# Bitcoiner_EB_Project_V1I1_Schematic.net
KiCad netlist of a schematic drawn in Altium Designer
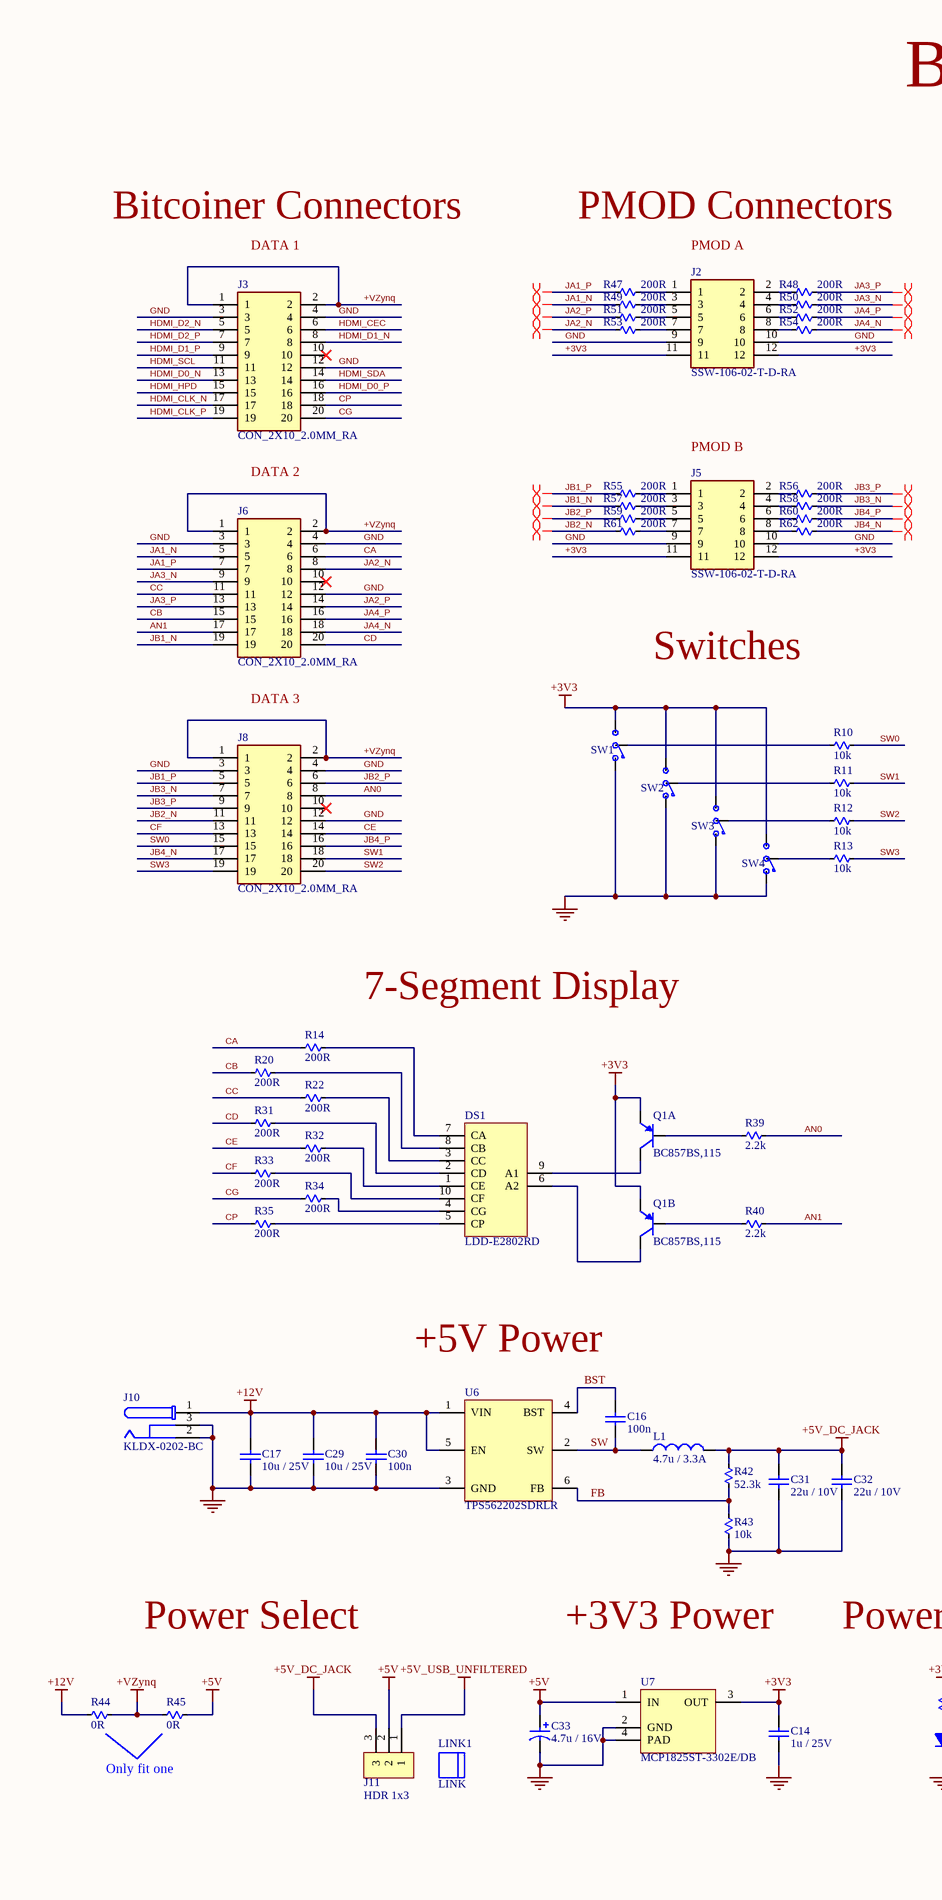
[diagram p0: Bitcoiner_EB_Project_V1I1_Schematic.SchDoc, left]
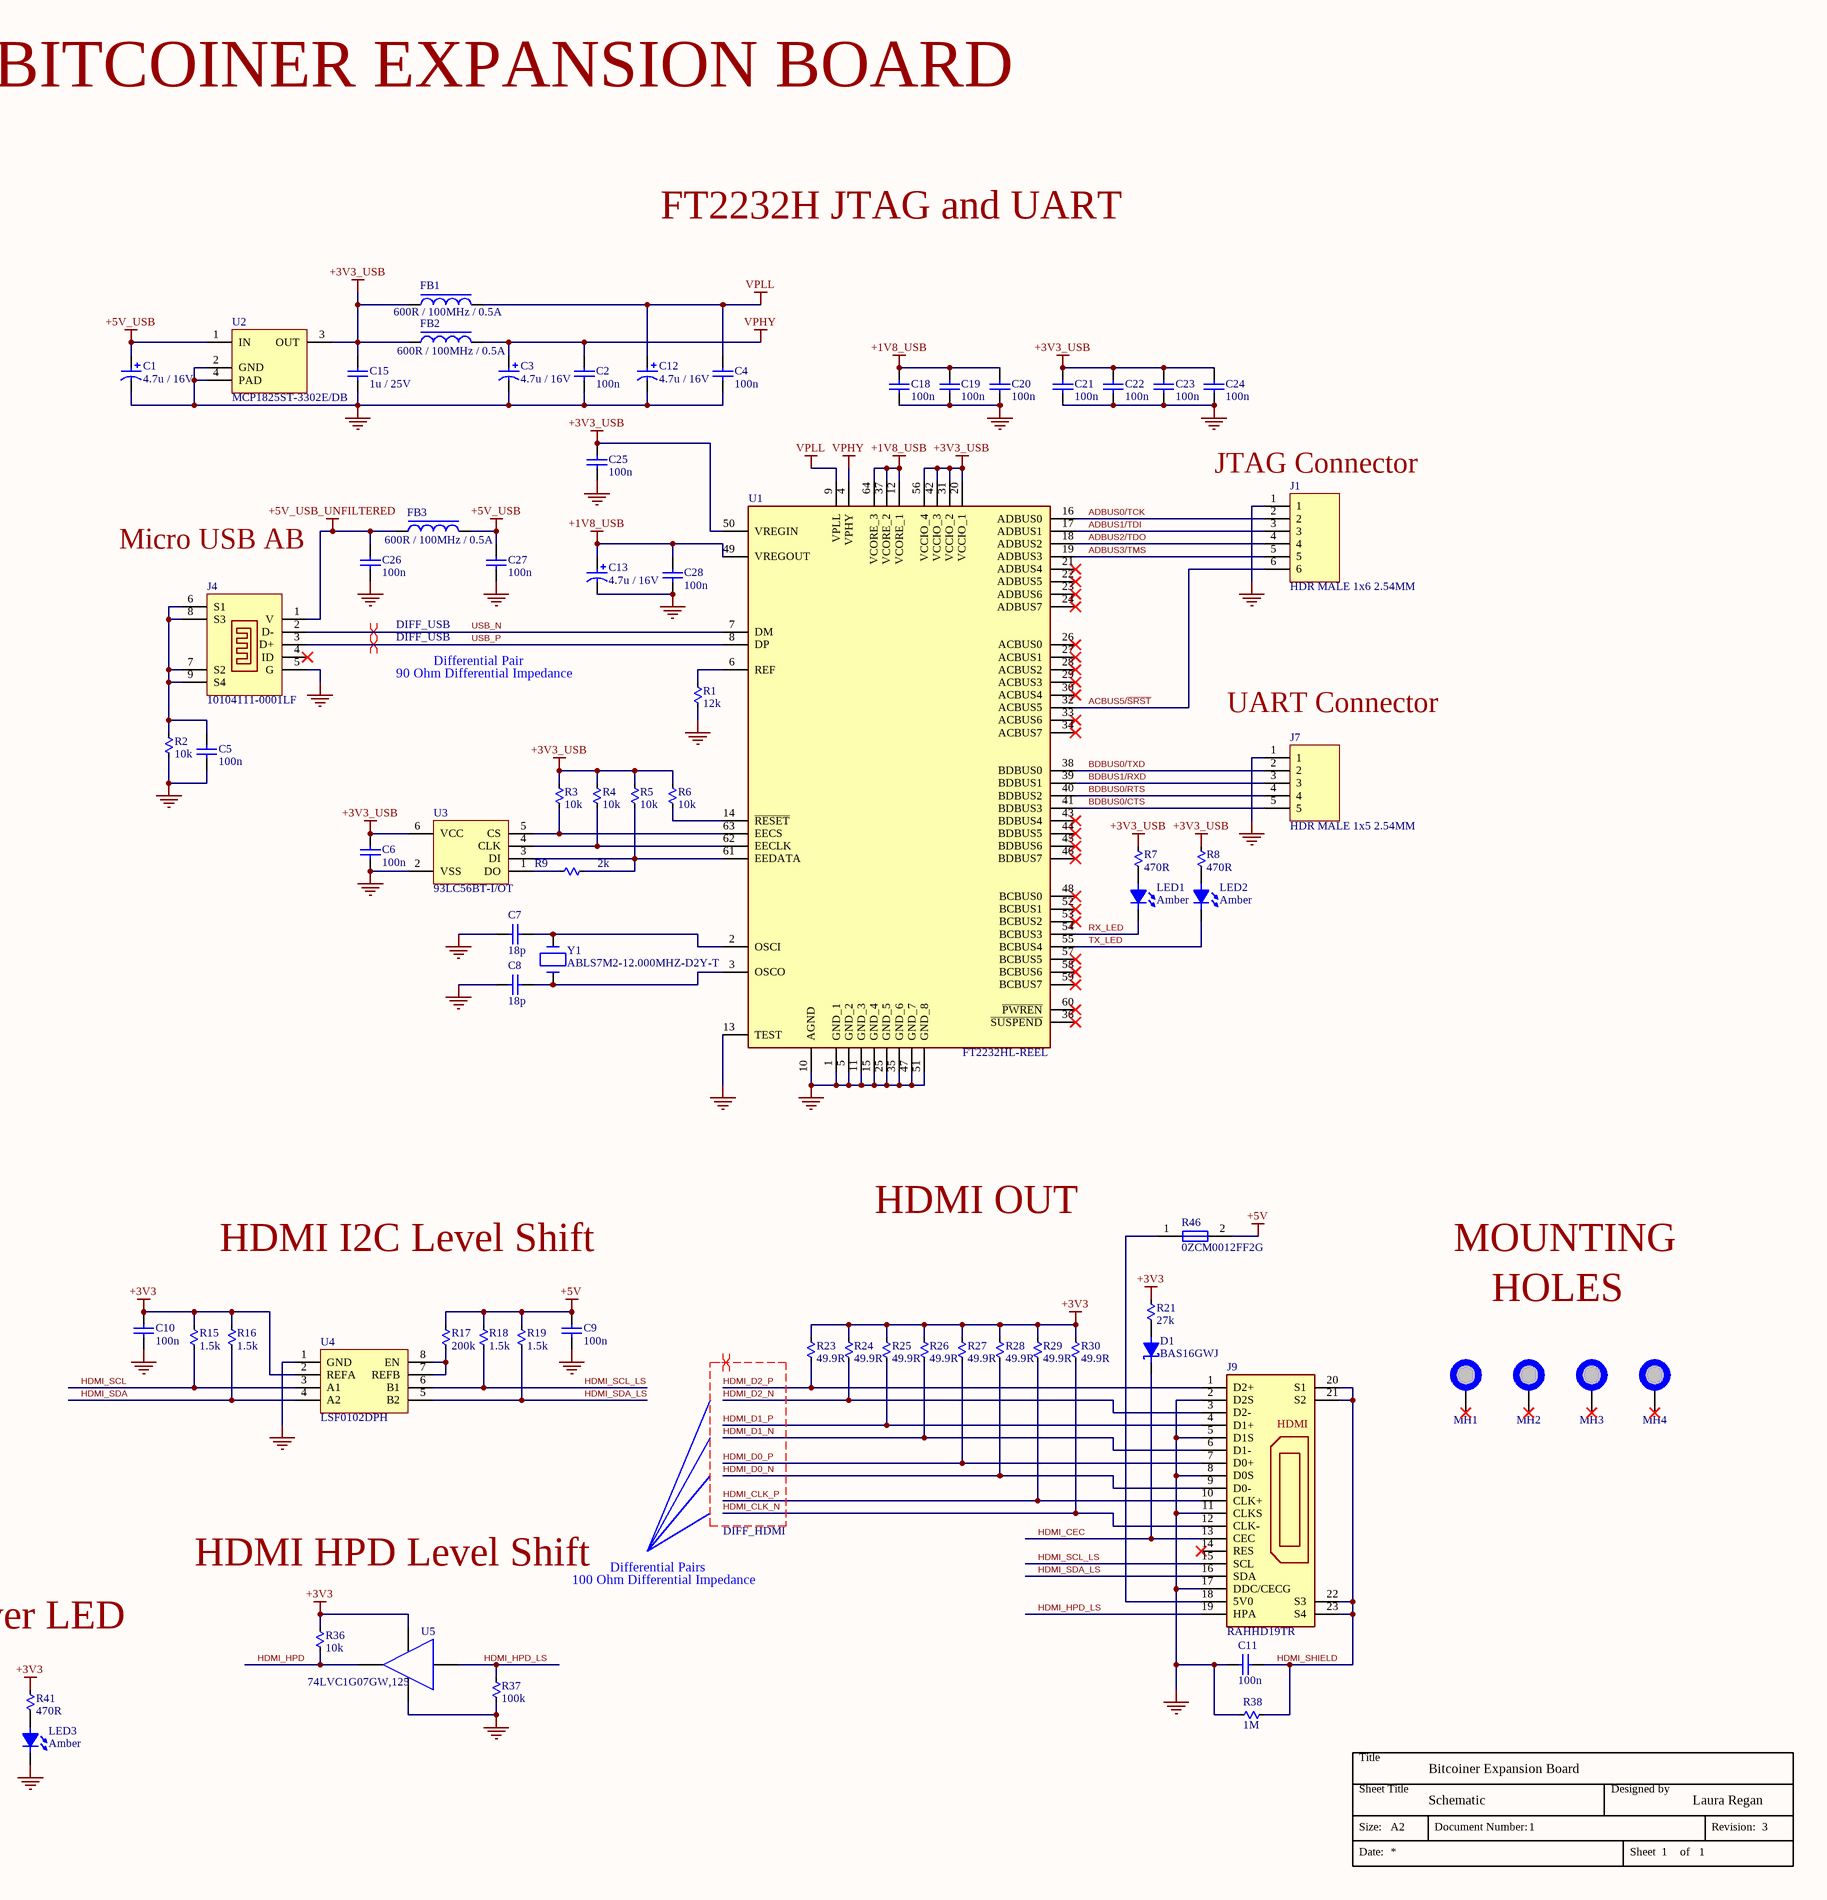
[diagram p1: Bitcoiner_EB_Project_V1I1_Schematic.SchDoc, right]

(export (version "E")
  (design (tool "Eeschema 10.0.6"))
  (components
    (comp (ref "*")
      (value "TitleBlock")
      (fields (field (name "SHEET TITLE") "Schematic") (field (name "SIZE") "A2"))
      (libsource (lib "Bitcoiner_EB_Project_V1I1") (part "TitleBlock"))
    )
    (comp (ref "C1")
      (value "4.7u / 16V")
      (footprint "C_TAN_A")
      (description "Tantalum capacitor 4.7 uF 16 VDC, T491A475K016AT, KEMET")
      (fields
        (field (name "MANUFACTURER") "KEMET")
        (field (name "MANUFACTURER PART NUMBER") "T491A475K016AT")
      )
      (libsource (lib "Bitcoiner_EB_Project_V1I1") (part "T491A475K016AT"))
    )
    (comp (ref "C2")
      (value "100n")
      (footprint "C0805")
      (fields
        (field (name "MANUFACTURER") "Kyocera AVX")
        (field (name "MANUFACTURER PART NUMBER") "08055C104KAT4A")
        (field (name "TOLERANCE") "10%")
      )
      (libsource (lib "Bitcoiner_EB_Project_V1I1") (part "08055C104KAT4A"))
    )
    (comp (ref "C3")
      (value "4.7u / 16V")
      (footprint "C_TAN_A")
      (description "Tantalum capacitor 4.7 uF 16 VDC, T491A475K016AT, KEMET")
      (fields
        (field (name "MANUFACTURER") "KEMET")
        (field (name "MANUFACTURER PART NUMBER") "T491A475K016AT")
      )
      (libsource (lib "Bitcoiner_EB_Project_V1I1") (part "T491A475K016AT"))
    )
    (comp (ref "C4")
      (value "100n")
      (footprint "C0805")
      (fields
        (field (name "MANUFACTURER") "Kyocera AVX")
        (field (name "MANUFACTURER PART NUMBER") "08055C104KAT4A")
        (field (name "TOLERANCE") "10%")
      )
      (libsource (lib "Bitcoiner_EB_Project_V1I1") (part "08055C104KAT4A"))
    )
    (comp (ref "C5")
      (value "100n")
      (footprint "C0805")
      (fields
        (field (name "MANUFACTURER") "Kyocera AVX")
        (field (name "MANUFACTURER PART NUMBER") "08055C104KAT4A")
        (field (name "TOLERANCE") "10%")
      )
      (libsource (lib "Bitcoiner_EB_Project_V1I1") (part "08055C104KAT4A"))
    )
    (comp (ref "C6")
      (value "100n")
      (footprint "C0805")
      (fields
        (field (name "MANUFACTURER") "Kyocera AVX")
        (field (name "MANUFACTURER PART NUMBER") "08055C104KAT4A")
        (field (name "TOLERANCE") "10%")
      )
      (libsource (lib "Bitcoiner_EB_Project_V1I1") (part "08055C104KAT4A"))
    )
    (comp (ref "C7")
      (value "18p")
      (footprint "C0805")
      (description "Cap Ceramic 18pF 50V C0G 5% Pad SMD 0805 125°C Extreme Low ESR Bag")
      (fields
        (field (name "MANUFACTURER") "KEMET")
        (field (name "MANUFACTURER PART NUMBER") "C0805C180J5GAC")
      )
      (libsource (lib "Bitcoiner_EB_Project_V1I1") (part "C0805C180J5GAC"))
    )
    (comp (ref "C8")
      (value "18p")
      (footprint "C0805")
      (description "Cap Ceramic 18pF 50V C0G 5% Pad SMD 0805 125°C Extreme Low ESR Bag")
      (fields
        (field (name "MANUFACTURER") "KEMET")
        (field (name "MANUFACTURER PART NUMBER") "C0805C180J5GAC")
      )
      (libsource (lib "Bitcoiner_EB_Project_V1I1") (part "C0805C180J5GAC"))
    )
    (comp (ref "C9")
      (value "100n")
      (footprint "C0805")
      (fields
        (field (name "MANUFACTURER") "Kyocera AVX")
        (field (name "MANUFACTURER PART NUMBER") "08055C104KAT4A")
        (field (name "TOLERANCE") "10%")
      )
      (libsource (lib "Bitcoiner_EB_Project_V1I1") (part "08055C104KAT4A"))
    )
    (comp (ref "C10")
      (value "100n")
      (footprint "C0805")
      (fields
        (field (name "MANUFACTURER") "Kyocera AVX")
        (field (name "MANUFACTURER PART NUMBER") "08055C104KAT4A")
        (field (name "TOLERANCE") "10%")
      )
      (libsource (lib "Bitcoiner_EB_Project_V1I1") (part "08055C104KAT4A"))
    )
    (comp (ref "C11")
      (value "100n")
      (footprint "C0805")
      (fields
        (field (name "MANUFACTURER") "Kyocera AVX")
        (field (name "MANUFACTURER PART NUMBER") "08055C104KAT4A")
        (field (name "TOLERANCE") "10%")
      )
      (libsource (lib "Bitcoiner_EB_Project_V1I1") (part "08055C104KAT4A"))
    )
    (comp (ref "C12")
      (value "4.7u / 16V")
      (footprint "C_TAN_A")
      (description "Tantalum capacitor 4.7 uF 16 VDC, T491A475K016AT, KEMET")
      (fields
        (field (name "MANUFACTURER") "KEMET")
        (field (name "MANUFACTURER PART NUMBER") "T491A475K016AT")
      )
      (libsource (lib "Bitcoiner_EB_Project_V1I1") (part "T491A475K016AT"))
    )
    (comp (ref "C13")
      (value "4.7u / 16V")
      (footprint "C_TAN_A")
      (description "Tantalum capacitor 4.7 uF 16 VDC, T491A475K016AT, KEMET")
      (fields
        (field (name "MANUFACTURER") "KEMET")
        (field (name "MANUFACTURER PART NUMBER") "T491A475K016AT")
      )
      (libsource (lib "Bitcoiner_EB_Project_V1I1") (part "T491A475K016AT"))
    )
    (comp (ref "C14")
      (value "1u / 25V")
      (footprint "C0805")
      (description "Cap Ceramic 1uF 25V X7R 10% SMD 0805 125C Plastic T/R")
      (fields
        (field (name "MANUFACTURER") "KEMET")
        (field (name "MANUFACTURER PART NUMBER") "C0805C105K3RAC7210")
      )
      (libsource (lib "Bitcoiner_EB_Project_V1I1") (part "C0805C105K3RAC7210"))
    )
    (comp (ref "C15")
      (value "1u / 25V")
      (footprint "C0805")
      (description "Cap Ceramic 1uF 25V X7R 10% SMD 0805 125C Plastic T/R")
      (fields
        (field (name "MANUFACTURER") "KEMET")
        (field (name "MANUFACTURER PART NUMBER") "C0805C105K3RAC7210")
      )
      (libsource (lib "Bitcoiner_EB_Project_V1I1") (part "C0805C105K3RAC7210"))
    )
    (comp (ref "C16")
      (value "100n")
      (footprint "C0805")
      (fields
        (field (name "MANUFACTURER") "Kyocera AVX")
        (field (name "MANUFACTURER PART NUMBER") "08055C104KAT4A")
        (field (name "TOLERANCE") "10%")
      )
      (libsource (lib "Bitcoiner_EB_Project_V1I1") (part "08055C104KAT4A"))
    )
    (comp (ref "C17")
      (value "10u / 25V")
      (footprint "C0805")
      (description "CAP CER 10UF 25V X5R 0805")
      (fields
        (field (name "MANUFACTURER") "Murata")
        (field (name "MANUFACTURER PART NUMBER") "GRM21BR61E106KA73K")
      )
      (libsource (lib "Bitcoiner_EB_Project_V1I1") (part "GRM21BR61E106KA73K"))
    )
    (comp (ref "C18")
      (value "100n")
      (footprint "C0805")
      (fields
        (field (name "MANUFACTURER") "Kyocera AVX")
        (field (name "MANUFACTURER PART NUMBER") "08055C104KAT4A")
        (field (name "TOLERANCE") "10%")
      )
      (libsource (lib "Bitcoiner_EB_Project_V1I1") (part "08055C104KAT4A"))
    )
    (comp (ref "C19")
      (value "100n")
      (footprint "C0805")
      (fields
        (field (name "MANUFACTURER") "Kyocera AVX")
        (field (name "MANUFACTURER PART NUMBER") "08055C104KAT4A")
        (field (name "TOLERANCE") "10%")
      )
      (libsource (lib "Bitcoiner_EB_Project_V1I1") (part "08055C104KAT4A"))
    )
    (comp (ref "C20")
      (value "100n")
      (footprint "C0805")
      (fields
        (field (name "MANUFACTURER") "Kyocera AVX")
        (field (name "MANUFACTURER PART NUMBER") "08055C104KAT4A")
        (field (name "TOLERANCE") "10%")
      )
      (libsource (lib "Bitcoiner_EB_Project_V1I1") (part "08055C104KAT4A"))
    )
    (comp (ref "C21")
      (value "100n")
      (footprint "C0805")
      (fields
        (field (name "MANUFACTURER") "Kyocera AVX")
        (field (name "MANUFACTURER PART NUMBER") "08055C104KAT4A")
        (field (name "TOLERANCE") "10%")
      )
      (libsource (lib "Bitcoiner_EB_Project_V1I1") (part "08055C104KAT4A"))
    )
    (comp (ref "C22")
      (value "100n")
      (footprint "C0805")
      (fields
        (field (name "MANUFACTURER") "Kyocera AVX")
        (field (name "MANUFACTURER PART NUMBER") "08055C104KAT4A")
        (field (name "TOLERANCE") "10%")
      )
      (libsource (lib "Bitcoiner_EB_Project_V1I1") (part "08055C104KAT4A"))
    )
    (comp (ref "C23")
      (value "100n")
      (footprint "C0805")
      (fields
        (field (name "MANUFACTURER") "Kyocera AVX")
        (field (name "MANUFACTURER PART NUMBER") "08055C104KAT4A")
        (field (name "TOLERANCE") "10%")
      )
      (libsource (lib "Bitcoiner_EB_Project_V1I1") (part "08055C104KAT4A"))
    )
    (comp (ref "C24")
      (value "100n")
      (footprint "C0805")
      (fields
        (field (name "MANUFACTURER") "Kyocera AVX")
        (field (name "MANUFACTURER PART NUMBER") "08055C104KAT4A")
        (field (name "TOLERANCE") "10%")
      )
      (libsource (lib "Bitcoiner_EB_Project_V1I1") (part "08055C104KAT4A"))
    )
    (comp (ref "C25")
      (value "100n")
      (footprint "C0805")
      (fields
        (field (name "MANUFACTURER") "Kyocera AVX")
        (field (name "MANUFACTURER PART NUMBER") "08055C104KAT4A")
        (field (name "TOLERANCE") "10%")
      )
      (libsource (lib "Bitcoiner_EB_Project_V1I1") (part "08055C104KAT4A"))
    )
    (comp (ref "C26")
      (value "100n")
      (footprint "C0805")
      (fields
        (field (name "MANUFACTURER") "Kyocera AVX")
        (field (name "MANUFACTURER PART NUMBER") "08055C104KAT4A")
        (field (name "TOLERANCE") "10%")
      )
      (libsource (lib "Bitcoiner_EB_Project_V1I1") (part "08055C104KAT4A"))
    )
    (comp (ref "C27")
      (value "100n")
      (footprint "C0805")
      (fields
        (field (name "MANUFACTURER") "Kyocera AVX")
        (field (name "MANUFACTURER PART NUMBER") "08055C104KAT4A")
        (field (name "TOLERANCE") "10%")
      )
      (libsource (lib "Bitcoiner_EB_Project_V1I1") (part "08055C104KAT4A"))
    )
    (comp (ref "C28")
      (value "100n")
      (footprint "C0805")
      (fields
        (field (name "MANUFACTURER") "Kyocera AVX")
        (field (name "MANUFACTURER PART NUMBER") "08055C104KAT4A")
        (field (name "TOLERANCE") "10%")
      )
      (libsource (lib "Bitcoiner_EB_Project_V1I1") (part "08055C104KAT4A"))
    )
    (comp (ref "C29")
      (value "10u / 25V")
      (footprint "C0805")
      (description "CAP CER 10UF 25V X5R 0805")
      (fields
        (field (name "MANUFACTURER") "Murata")
        (field (name "MANUFACTURER PART NUMBER") "GRM21BR61E106KA73K")
      )
      (libsource (lib "Bitcoiner_EB_Project_V1I1") (part "GRM21BR61E106KA73K"))
    )
    (comp (ref "C30")
      (value "100n")
      (footprint "C0805")
      (fields
        (field (name "MANUFACTURER") "Kyocera AVX")
        (field (name "MANUFACTURER PART NUMBER") "08055C104KAT4A")
        (field (name "TOLERANCE") "10%")
      )
      (libsource (lib "Bitcoiner_EB_Project_V1I1") (part "08055C104KAT4A"))
    )
    (comp (ref "C31")
      (value "22u / 10V")
      (footprint "C0805")
      (description "Cap Ceramic 22uF 10V X5R 20% SMD 0805 85C Cardboard T/R")
      (fields
        (field (name "MANUFACTURER") "Samsung")
        (field (name "MANUFACTURER PART NUMBER") "CL21A226MPCLRNC")
      )
      (libsource (lib "Bitcoiner_EB_Project_V1I1") (part "CL21A226MPCLRNC"))
    )
    (comp (ref "C32")
      (value "22u / 10V")
      (footprint "C0805")
      (description "Cap Ceramic 22uF 10V X5R 20% SMD 0805 85C Cardboard T/R")
      (fields
        (field (name "MANUFACTURER") "Samsung")
        (field (name "MANUFACTURER PART NUMBER") "CL21A226MPCLRNC")
      )
      (libsource (lib "Bitcoiner_EB_Project_V1I1") (part "CL21A226MPCLRNC"))
    )
    (comp (ref "C33")
      (value "4.7u / 16V")
      (footprint "C_TAN_A")
      (description "Tantalum capacitor 4.7 uF 16 VDC, T491A475K016AT, KEMET")
      (fields
        (field (name "MANUFACTURER") "KEMET")
        (field (name "MANUFACTURER PART NUMBER") "T491A475K016AT")
      )
      (libsource (lib "Bitcoiner_EB_Project_V1I1") (part "T491A475K016AT"))
    )
    (comp (ref "D1")
      (value "BAS16GWJ")
      (footprint "SOD123")
      (description "High-speed switching diode BAS16GW/SOD2/REEL 13 Q1/T1 S\"")
      (fields (field (name "MANUFACTURER") "Nexperia"))
      (libsource (lib "Bitcoiner_EB_Project_V1I1") (part "BAS16GWJ"))
    )
    (comp (ref "DS1")
      (value "LDD-E2802RD")
      (footprint "LDD-E2802RD")
      (description "Dual Digit 565 nm Green 0.28 inch Common Anode Seven Segment Display")
      (fields (field (name "MANUFACTURER") "Lumex"))
      (libsource (lib "Bitcoiner_EB_Project_V1I1") (part "LDD-E2802RD"))
    )
    (comp (ref "FB1")
      (value "600R / 100MHz / 0.5A")
      (footprint "R0805")
      (description "TDK         MMZ2012R601AT000            FERRITE BEAD, 0.2OHM, 500MA, 0805")
      (fields
        (field (name "MANUFACTURER") "TDK")
        (field (name "MANUFACTURER PART NUMBER") "MMZ2012R601AT000")
      )
      (libsource (lib "Bitcoiner_EB_Project_V1I1") (part "MMZ2012R601AT000"))
    )
    (comp (ref "FB2")
      (value "600R / 100MHz / 0.5A")
      (footprint "R0805")
      (description "TDK         MMZ2012R601AT000            FERRITE BEAD, 0.2OHM, 500MA, 0805")
      (fields
        (field (name "MANUFACTURER") "TDK")
        (field (name "MANUFACTURER PART NUMBER") "MMZ2012R601AT000")
      )
      (libsource (lib "Bitcoiner_EB_Project_V1I1") (part "MMZ2012R601AT000"))
    )
    (comp (ref "FB3")
      (value "600R / 100MHz / 0.5A")
      (footprint "R0805")
      (description "TDK         MMZ2012R601AT000            FERRITE BEAD, 0.2OHM, 500MA, 0805")
      (fields
        (field (name "MANUFACTURER") "TDK")
        (field (name "MANUFACTURER PART NUMBER") "MMZ2012R601AT000")
      )
      (libsource (lib "Bitcoiner_EB_Project_V1I1") (part "MMZ2012R601AT000"))
    )
    (comp (ref "J1")
      (value "HDR MALE 1x6 2.54MM")
      (footprint "HDR_MALE_1X6_2.54MM")
      (fields
        (field (name "MANUFACTURER") "Amphenol")
        (field (name "MANUFACTURER PART NUMBER") "G800W302018EU")
      )
      (libsource (lib "Bitcoiner_EB_Project_V1I1") (part "G800W302018EU"))
    )
    (comp (ref "J2")
      (value "SSW-106-02-T-D-RA")
      (footprint "SSW-106-XX-YYY-D-RA")
      (description "Connector")
      (fields (field (name "MOUSER2 PART NUMBER") "200-SSW10602TDRA") (field (name "MANUFACTURER") "SAMTEC"))
      (libsource (lib "Bitcoiner_EB_Project_V1I1") (part "SSW-106-02-T-D-RA"))
    )
    (comp (ref "J3")
      (value "CON_2X10_2.0MM_RA")
      (footprint "CON_2X10_2.0MM_RA")
      (libsource (lib "Bitcoiner_EB_Project_V1I1") (part "CON_2X10_2.0MM_RA"))
    )
    (comp (ref "J4")
      (value "10104111-0001LF")
      (footprint "101041110001LF")
      (description "Conn USB Type A/B RCP 5 POS 0.65mm Solder RA SMD 5 Terminal 1 Port T/R")
      (fields (field (name "MANUFACTURER") "AMPHENOL ICC (FCI)"))
      (libsource (lib "Bitcoiner_EB_Project_V1I1") (part "10104111-0001LF"))
    )
    (comp (ref "J5")
      (value "SSW-106-02-T-D-RA")
      (footprint "SSW-106-XX-YYY-D-RA")
      (description "Connector")
      (fields (field (name "MOUSER2 PART NUMBER") "200-SSW10602TDRA") (field (name "MANUFACTURER") "SAMTEC"))
      (libsource (lib "Bitcoiner_EB_Project_V1I1") (part "SSW-106-02-T-D-RA"))
    )
    (comp (ref "J6")
      (value "CON_2X10_2.0MM_RA")
      (footprint "CON_2X10_2.0MM_RA")
      (libsource (lib "Bitcoiner_EB_Project_V1I1") (part "CON_2X10_2.0MM_RA"))
    )
    (comp (ref "J7")
      (value "HDR MALE 1x5 2.54MM")
      (footprint "Hdr_Female_1x5_2.54mm")
      (description "HDR FEMALE 1x5 2.54MM")
      (fields
        (field (name "MANUFACTURER") "Amphenol ICC")
        (field (name "MANUFACTURER PART NUMBER") "10129378-905001BLF")
      )
      (libsource (lib "Bitcoiner_EB_Project_V1I1") (part "10129378-905001BLF"))
    )
    (comp (ref "J8")
      (value "CON_2X10_2.0MM_RA")
      (footprint "CON_2X10_2.0MM_RA")
      (libsource (lib "Bitcoiner_EB_Project_V1I1") (part "CON_2X10_2.0MM_RA"))
    )
    (comp (ref "J9")
      (value "RAHHD19TR")
      (footprint "RAHHD19TR")
      (description "HDMI Connector")
      (fields (field (name "MANUFACTURER") "Switchcraft Conxall"))
      (libsource (lib "Bitcoiner_EB_Project_V1I1") (part "RAHHD19TR"))
    )
    (comp (ref "J10")
      (value "KLDX-0202-BC")
      (footprint "KLDX-0202-BC")
      (description "Conn Power PIN 2 POS Solder RA Thru-Hole 3 Terminal 1 Port")
      (fields (field (name "MANUFACTURER") "Kycon"))
      (libsource (lib "Bitcoiner_EB_Project_V1I1") (part "KLDX-0202-BC"))
    )
    (comp (ref "J11")
      (value "HDR 1x3")
      (footprint "HDR_Male_1x3_2.54mm")
      (description "HDR MALE 1x3 2.54MM")
      (fields
        (field (name "MANUFACTURER") "Amphenol")
        (field (name "MANUFACTURER PART NUMBER") "G800W305018EU")
      )
      (libsource (lib "Bitcoiner_EB_Project_V1I1") (part "G800W305018EU"))
    )
    (comp (ref "L1")
      (value "4.7u / 3.3A")
      (footprint "TYS6045")
      (description "Pwrind, SMT, Shld, Lrated / 6.0X6.0X4.5MM / Uom=ea / Wire Wound Inductive / Fixed Inductor")
      (fields
        (field (name "MANUFACTURER") "Laird Steward")
        (field (name "MANUFACTURER PART NUMBER") "TYS60454R7M-10")
      )
      (libsource (lib "Bitcoiner_EB_Project_V1I1") (part "TYS60454R7M-10"))
    )
    (comp (ref "LED1")
      (value "Amber")
      (footprint "LED0603")
      (description "LED Uni-Color Amber 609nm Automotive 2-Pin Chip 0603(1608Metric) T/R")
      (fields (field (name "MANUFACTURER") "Inolux") (field (name "MANUFACTURER PART NUMBER") "IN-S63AT5A"))
      (libsource (lib "Bitcoiner_EB_Project_V1I1") (part "IN-S63AT5A"))
    )
    (comp (ref "LED2")
      (value "Amber")
      (footprint "LED0603")
      (description "LED Uni-Color Amber 609nm Automotive 2-Pin Chip 0603(1608Metric) T/R")
      (fields (field (name "MANUFACTURER") "Inolux") (field (name "MANUFACTURER PART NUMBER") "IN-S63AT5A"))
      (libsource (lib "Bitcoiner_EB_Project_V1I1") (part "IN-S63AT5A"))
    )
    (comp (ref "LED3")
      (value "Amber")
      (footprint "LED0603")
      (description "LED Uni-Color Amber 609nm Automotive 2-Pin Chip 0603(1608Metric) T/R")
      (fields (field (name "MANUFACTURER") "Inolux") (field (name "MANUFACTURER PART NUMBER") "IN-S63AT5A"))
      (libsource (lib "Bitcoiner_EB_Project_V1I1") (part "IN-S63AT5A"))
    )
    (comp (ref "LINK1")
      (value "LINK")
      (description "CONN SHUNT 2POS OPEN 2.54MM")
      (fields
        (field (name "MANUFACTURER") "TE Connectivity")
        (field (name "MANUFACTURER PART NUMBER") "382811-8")
      )
      (libsource (lib "Bitcoiner_EB_Project_V1I1") (part "382811-8"))
    )
    (comp (ref "MH1")
      (value "MH_7.4MMNC_3.2MMD")
      (footprint "MH_7.4MMD_3.2MMD_NON_COPPER_NPTH")
      (description "Mounting Hole 7.4mm Diameter (Non Copper), 3.2 Drill NPTH")
      (libsource (lib "Bitcoiner_EB_Project_V1I1") (part "MH_7.4MMNC_3.2MMD"))
    )
    (comp (ref "MH2")
      (value "MH_7.4MMNC_3.2MMD")
      (footprint "MH_7.4MMD_3.2MMD_NON_COPPER_NPTH")
      (description "Mounting Hole 7.4mm Diameter (Non Copper), 3.2 Drill NPTH")
      (libsource (lib "Bitcoiner_EB_Project_V1I1") (part "MH_7.4MMNC_3.2MMD"))
    )
    (comp (ref "MH3")
      (value "MH_7.4MMNC_3.2MMD")
      (footprint "MH_7.4MMD_3.2MMD_NON_COPPER_NPTH")
      (description "Mounting Hole 7.4mm Diameter (Non Copper), 3.2 Drill NPTH")
      (libsource (lib "Bitcoiner_EB_Project_V1I1") (part "MH_7.4MMNC_3.2MMD"))
    )
    (comp (ref "MH4")
      (value "MH_7.4MMNC_3.2MMD")
      (footprint "MH_7.4MMD_3.2MMD_NON_COPPER_NPTH")
      (description "Mounting Hole 7.4mm Diameter (Non Copper), 3.2 Drill NPTH")
      (libsource (lib "Bitcoiner_EB_Project_V1I1") (part "MH_7.4MMNC_3.2MMD"))
    )
    (comp (ref "Q1")
      (value "BC857BS,115")
      (footprint "SOT363")
      (description "NEXPERIA - BC857BS,115 - TRANSISTOR, DUAL, PNP, SC-88")
      (fields (field (name "MANUFACTURER") "Nexperia"))
      (libsource (lib "Bitcoiner_EB_Project_V1I1") (part "BC857BS,115"))
    )
    (comp (ref "R1")
      (value "12k")
      (footprint "R0805")
      (description "Res Thick Film 0805 12K Ohm 1% 0.125W(1/8W) ±100ppm/C Molded SMD Paper T/R")
      (fields
        (field (name "MANUFACTURER") "Yageo")
        (field (name "MANUFACTURER PART NUMBER") "RC0805FR-0712KL")
      )
      (libsource (lib "Bitcoiner_EB_Project_V1I1") (part "RC0805FR-0712KL"))
    )
    (comp (ref "R2")
      (value "10k")
      (footprint "R0805")
      (description "RES SMD 10K OHM 1% 1/8W 0805")
      (fields
        (field (name "MANUFACTURER") "Yageo")
        (field (name "MANUFACTURER PART NUMBER") "RC0805FR-0710KL")
      )
      (libsource (lib "Bitcoiner_EB_Project_V1I1") (part "RC0805FR-0710KL"))
    )
    (comp (ref "R3")
      (value "10k")
      (footprint "R0805")
      (description "RES SMD 10K OHM 1% 1/8W 0805")
      (fields
        (field (name "MANUFACTURER") "Yageo")
        (field (name "MANUFACTURER PART NUMBER") "RC0805FR-0710KL")
      )
      (libsource (lib "Bitcoiner_EB_Project_V1I1") (part "RC0805FR-0710KL"))
    )
    (comp (ref "R4")
      (value "10k")
      (footprint "R0805")
      (description "RES SMD 10K OHM 1% 1/8W 0805")
      (fields
        (field (name "MANUFACTURER") "Yageo")
        (field (name "MANUFACTURER PART NUMBER") "RC0805FR-0710KL")
      )
      (libsource (lib "Bitcoiner_EB_Project_V1I1") (part "RC0805FR-0710KL"))
    )
    (comp (ref "R5")
      (value "10k")
      (footprint "R0805")
      (description "RES SMD 10K OHM 1% 1/8W 0805")
      (fields
        (field (name "MANUFACTURER") "Yageo")
        (field (name "MANUFACTURER PART NUMBER") "RC0805FR-0710KL")
      )
      (libsource (lib "Bitcoiner_EB_Project_V1I1") (part "RC0805FR-0710KL"))
    )
    (comp (ref "R6")
      (value "10k")
      (footprint "R0805")
      (description "RES SMD 10K OHM 1% 1/8W 0805")
      (fields
        (field (name "MANUFACTURER") "Yageo")
        (field (name "MANUFACTURER PART NUMBER") "RC0805FR-0710KL")
      )
      (libsource (lib "Bitcoiner_EB_Project_V1I1") (part "RC0805FR-0710KL"))
    )
    (comp (ref "R7")
      (value "470R")
      (footprint "R0805")
      (description "Res Thick Film 0805 470 Ohm 1% 1/8W +/-100ppm/ßC Molded SMD Paper T/R")
      (fields
        (field (name "MANUFACTURER") "Yageo")
        (field (name "MANUFACTURER PART NUMBER") "RC0805FR-07470RL")
      )
      (libsource (lib "Bitcoiner_EB_Project_V1I1") (part "RC0805FR-07470RL"))
    )
    (comp (ref "R8")
      (value "470R")
      (footprint "R0805")
      (description "Res Thick Film 0805 470 Ohm 1% 1/8W +/-100ppm/ßC Molded SMD Paper T/R")
      (fields
        (field (name "MANUFACTURER") "Yageo")
        (field (name "MANUFACTURER PART NUMBER") "RC0805FR-07470RL")
      )
      (libsource (lib "Bitcoiner_EB_Project_V1I1") (part "RC0805FR-07470RL"))
    )
    (comp (ref "R9")
      (value "2k")
      (footprint "R0805")
      (description "Res Thick Film 0805 2K Ohm 1% 1/8W 100ppm/C Molded SMD SMD Paper T/R")
      (fields
        (field (name "MANUFACTURER") "Yageo")
        (field (name "MANUFACTURER PART NUMBER") "RC0805FR-102KL")
      )
      (libsource (lib "Bitcoiner_EB_Project_V1I1") (part "RC0805FR-102KL"))
    )
    (comp (ref "R10")
      (value "10k")
      (footprint "R0805")
      (description "RES SMD 10K OHM 1% 1/8W 0805")
      (fields
        (field (name "MANUFACTURER") "Yageo")
        (field (name "MANUFACTURER PART NUMBER") "RC0805FR-0710KL")
      )
      (libsource (lib "Bitcoiner_EB_Project_V1I1") (part "RC0805FR-0710KL"))
    )
    (comp (ref "R11")
      (value "10k")
      (footprint "R0805")
      (description "RES SMD 10K OHM 1% 1/8W 0805")
      (fields
        (field (name "MANUFACTURER") "Yageo")
        (field (name "MANUFACTURER PART NUMBER") "RC0805FR-0710KL")
      )
      (libsource (lib "Bitcoiner_EB_Project_V1I1") (part "RC0805FR-0710KL"))
    )
    (comp (ref "R12")
      (value "10k")
      (footprint "R0805")
      (description "RES SMD 10K OHM 1% 1/8W 0805")
      (fields
        (field (name "MANUFACTURER") "Yageo")
        (field (name "MANUFACTURER PART NUMBER") "RC0805FR-0710KL")
      )
      (libsource (lib "Bitcoiner_EB_Project_V1I1") (part "RC0805FR-0710KL"))
    )
    (comp (ref "R13")
      (value "10k")
      (footprint "R0805")
      (description "RES SMD 10K OHM 1% 1/8W 0805")
      (fields
        (field (name "MANUFACTURER") "Yageo")
        (field (name "MANUFACTURER PART NUMBER") "RC0805FR-0710KL")
      )
      (libsource (lib "Bitcoiner_EB_Project_V1I1") (part "RC0805FR-0710KL"))
    )
    (comp (ref "R14")
      (value "200R")
      (footprint "R0805")
      (description "Res Thick Film 2.0 x 1.2 mm 200 Ohm 1% 0.125W(1/8W) 100ppm/ C Molded SMD Paper T/R")
      (fields
        (field (name "MANUFACTURER") "Yageo")
        (field (name "MANUFACTURER PART NUMBER") "RC0805FR-07200RL")
      )
      (libsource (lib "Bitcoiner_EB_Project_V1I1") (part "RC0805FR-07200RL"))
    )
    (comp (ref "R15")
      (value "1.5k")
      (footprint "R0805")
      (description "Res Thick Film 0805 1.5K Ohm 1% 0.125W(1/8W) ±100ppm/C Molded SMD Paper T/R")
      (fields
        (field (name "MANUFACTURER") "Yageo")
        (field (name "MANUFACTURER PART NUMBER") "RC0805FR-071K5L")
      )
      (libsource (lib "Bitcoiner_EB_Project_V1I1") (part "RC0805FR-071K5L"))
    )
    (comp (ref "R16")
      (value "1.5k")
      (footprint "R0805")
      (description "Res Thick Film 0805 1.5K Ohm 1% 0.125W(1/8W) ±100ppm/C Molded SMD Paper T/R")
      (fields
        (field (name "MANUFACTURER") "Yageo")
        (field (name "MANUFACTURER PART NUMBER") "RC0805FR-071K5L")
      )
      (libsource (lib "Bitcoiner_EB_Project_V1I1") (part "RC0805FR-071K5L"))
    )
    (comp (ref "R17")
      (value "200k")
      (footprint "R0805")
      (description "YAGEO - RC0805FR-07200KL - RES, THICK FILM, 200K, 1%, 0.125W, 0805, REEL")
      (fields
        (field (name "MANUFACTURER") "Yageo")
        (field (name "MANUFACTURER PART NUMBER") "RC0805FR-07200KL")
      )
      (libsource (lib "Bitcoiner_EB_Project_V1I1") (part "RC0805FR-07200KL"))
    )
    (comp (ref "R18")
      (value "1.5k")
      (footprint "R0805")
      (description "Res Thick Film 0805 1.5K Ohm 1% 0.125W(1/8W) ±100ppm/C Molded SMD Paper T/R")
      (fields
        (field (name "MANUFACTURER") "Yageo")
        (field (name "MANUFACTURER PART NUMBER") "RC0805FR-071K5L")
      )
      (libsource (lib "Bitcoiner_EB_Project_V1I1") (part "RC0805FR-071K5L"))
    )
    (comp (ref "R19")
      (value "1.5k")
      (footprint "R0805")
      (description "Res Thick Film 0805 1.5K Ohm 1% 0.125W(1/8W) ±100ppm/C Molded SMD Paper T/R")
      (fields
        (field (name "MANUFACTURER") "Yageo")
        (field (name "MANUFACTURER PART NUMBER") "RC0805FR-071K5L")
      )
      (libsource (lib "Bitcoiner_EB_Project_V1I1") (part "RC0805FR-071K5L"))
    )
    (comp (ref "R20")
      (value "200R")
      (footprint "R0805")
      (description "Res Thick Film 2.0 x 1.2 mm 200 Ohm 1% 0.125W(1/8W) 100ppm/ C Molded SMD Paper T/R")
      (fields
        (field (name "MANUFACTURER") "Yageo")
        (field (name "MANUFACTURER PART NUMBER") "RC0805FR-07200RL")
      )
      (libsource (lib "Bitcoiner_EB_Project_V1I1") (part "RC0805FR-07200RL"))
    )
    (comp (ref "R21")
      (value "27k")
      (footprint "R0805")
      (description "Chip Resistor Precision Grade Thick Film 0805 27kOhm 1% Paper T/R")
      (fields
        (field (name "MANUFACTURER") "Yageo")
        (field (name "MANUFACTURER PART NUMBER") "RE0805FRE0727KL")
      )
      (libsource (lib "Bitcoiner_EB_Project_V1I1") (part "RE0805FRE0727KL"))
    )
    (comp (ref "R22")
      (value "200R")
      (footprint "R0805")
      (description "Res Thick Film 2.0 x 1.2 mm 200 Ohm 1% 0.125W(1/8W) 100ppm/ C Molded SMD Paper T/R")
      (fields
        (field (name "MANUFACTURER") "Yageo")
        (field (name "MANUFACTURER PART NUMBER") "RC0805FR-07200RL")
      )
      (libsource (lib "Bitcoiner_EB_Project_V1I1") (part "RC0805FR-07200RL"))
    )
    (comp (ref "R23")
      (value "49.9R")
      (footprint "R0603")
      (description "Res Thick Film 0603 49.9 Ohm 1% 0.33W(1/3W) ±100ppm/°C Pad SMD Automotive T/R")
      (fields
        (field (name "MANUFACTURER") "Vishay Dale")
        (field (name "MANUFACTURER PART NUMBER") "CRCW060349R9FKEAHP")
      )
      (libsource (lib "Bitcoiner_EB_Project_V1I1") (part "CRCW060349R9FKEAHP"))
    )
    (comp (ref "R24")
      (value "49.9R")
      (footprint "R0603")
      (description "Res Thick Film 0603 49.9 Ohm 1% 0.33W(1/3W) ±100ppm/°C Pad SMD Automotive T/R")
      (fields
        (field (name "MANUFACTURER") "Vishay Dale")
        (field (name "MANUFACTURER PART NUMBER") "CRCW060349R9FKEAHP")
      )
      (libsource (lib "Bitcoiner_EB_Project_V1I1") (part "CRCW060349R9FKEAHP"))
    )
    (comp (ref "R25")
      (value "49.9R")
      (footprint "R0603")
      (description "Res Thick Film 0603 49.9 Ohm 1% 0.33W(1/3W) ±100ppm/°C Pad SMD Automotive T/R")
      (fields
        (field (name "MANUFACTURER") "Vishay Dale")
        (field (name "MANUFACTURER PART NUMBER") "CRCW060349R9FKEAHP")
      )
      (libsource (lib "Bitcoiner_EB_Project_V1I1") (part "CRCW060349R9FKEAHP"))
    )
    (comp (ref "R26")
      (value "49.9R")
      (footprint "R0603")
      (description "Res Thick Film 0603 49.9 Ohm 1% 0.33W(1/3W) ±100ppm/°C Pad SMD Automotive T/R")
      (fields
        (field (name "MANUFACTURER") "Vishay Dale")
        (field (name "MANUFACTURER PART NUMBER") "CRCW060349R9FKEAHP")
      )
      (libsource (lib "Bitcoiner_EB_Project_V1I1") (part "CRCW060349R9FKEAHP"))
    )
    (comp (ref "R27")
      (value "49.9R")
      (footprint "R0603")
      (description "Res Thick Film 0603 49.9 Ohm 1% 0.33W(1/3W) ±100ppm/°C Pad SMD Automotive T/R")
      (fields
        (field (name "MANUFACTURER") "Vishay Dale")
        (field (name "MANUFACTURER PART NUMBER") "CRCW060349R9FKEAHP")
      )
      (libsource (lib "Bitcoiner_EB_Project_V1I1") (part "CRCW060349R9FKEAHP"))
    )
    (comp (ref "R28")
      (value "49.9R")
      (footprint "R0603")
      (description "Res Thick Film 0603 49.9 Ohm 1% 0.33W(1/3W) ±100ppm/°C Pad SMD Automotive T/R")
      (fields
        (field (name "MANUFACTURER") "Vishay Dale")
        (field (name "MANUFACTURER PART NUMBER") "CRCW060349R9FKEAHP")
      )
      (libsource (lib "Bitcoiner_EB_Project_V1I1") (part "CRCW060349R9FKEAHP"))
    )
    (comp (ref "R29")
      (value "49.9R")
      (footprint "R0603")
      (description "Res Thick Film 0603 49.9 Ohm 1% 0.33W(1/3W) ±100ppm/°C Pad SMD Automotive T/R")
      (fields
        (field (name "MANUFACTURER") "Vishay Dale")
        (field (name "MANUFACTURER PART NUMBER") "CRCW060349R9FKEAHP")
      )
      (libsource (lib "Bitcoiner_EB_Project_V1I1") (part "CRCW060349R9FKEAHP"))
    )
    (comp (ref "R30")
      (value "49.9R")
      (footprint "R0603")
      (description "Res Thick Film 0603 49.9 Ohm 1% 0.33W(1/3W) ±100ppm/°C Pad SMD Automotive T/R")
      (fields
        (field (name "MANUFACTURER") "Vishay Dale")
        (field (name "MANUFACTURER PART NUMBER") "CRCW060349R9FKEAHP")
      )
      (libsource (lib "Bitcoiner_EB_Project_V1I1") (part "CRCW060349R9FKEAHP"))
    )
    (comp (ref "R31")
      (value "200R")
      (footprint "R0805")
      (description "Res Thick Film 2.0 x 1.2 mm 200 Ohm 1% 0.125W(1/8W) 100ppm/ C Molded SMD Paper T/R")
      (fields
        (field (name "MANUFACTURER") "Yageo")
        (field (name "MANUFACTURER PART NUMBER") "RC0805FR-07200RL")
      )
      (libsource (lib "Bitcoiner_EB_Project_V1I1") (part "RC0805FR-07200RL"))
    )
    (comp (ref "R32")
      (value "200R")
      (footprint "R0805")
      (description "Res Thick Film 2.0 x 1.2 mm 200 Ohm 1% 0.125W(1/8W) 100ppm/ C Molded SMD Paper T/R")
      (fields
        (field (name "MANUFACTURER") "Yageo")
        (field (name "MANUFACTURER PART NUMBER") "RC0805FR-07200RL")
      )
      (libsource (lib "Bitcoiner_EB_Project_V1I1") (part "RC0805FR-07200RL"))
    )
    (comp (ref "R33")
      (value "200R")
      (footprint "R0805")
      (description "Res Thick Film 2.0 x 1.2 mm 200 Ohm 1% 0.125W(1/8W) 100ppm/ C Molded SMD Paper T/R")
      (fields
        (field (name "MANUFACTURER") "Yageo")
        (field (name "MANUFACTURER PART NUMBER") "RC0805FR-07200RL")
      )
      (libsource (lib "Bitcoiner_EB_Project_V1I1") (part "RC0805FR-07200RL"))
    )
    (comp (ref "R34")
      (value "200R")
      (footprint "R0805")
      (description "Res Thick Film 2.0 x 1.2 mm 200 Ohm 1% 0.125W(1/8W) 100ppm/ C Molded SMD Paper T/R")
      (fields
        (field (name "MANUFACTURER") "Yageo")
        (field (name "MANUFACTURER PART NUMBER") "RC0805FR-07200RL")
      )
      (libsource (lib "Bitcoiner_EB_Project_V1I1") (part "RC0805FR-07200RL"))
    )
    (comp (ref "R35")
      (value "200R")
      (footprint "R0805")
      (description "Res Thick Film 2.0 x 1.2 mm 200 Ohm 1% 0.125W(1/8W) 100ppm/ C Molded SMD Paper T/R")
      (fields
        (field (name "MANUFACTURER") "Yageo")
        (field (name "MANUFACTURER PART NUMBER") "RC0805FR-07200RL")
      )
      (libsource (lib "Bitcoiner_EB_Project_V1I1") (part "RC0805FR-07200RL"))
    )
    (comp (ref "R36")
      (value "10k")
      (footprint "R0805")
      (description "RES SMD 10K OHM 1% 1/8W 0805")
      (fields
        (field (name "MANUFACTURER") "Yageo")
        (field (name "MANUFACTURER PART NUMBER") "RC0805FR-0710KL")
      )
      (libsource (lib "Bitcoiner_EB_Project_V1I1") (part "RC0805FR-0710KL"))
    )
    (comp (ref "R37")
      (value "100k")
      (footprint "R0805")
      (description "YAGEO         RC0805FR-07100KL            RES, THICK FILM, 100K, 1%, 0.125W, 0805, REEL")
      (fields
        (field (name "MANUFACTURER") "Yageo")
        (field (name "MANUFACTURER PART NUMBER") "RC0805FR-07100KL")
      )
      (libsource (lib "Bitcoiner_EB_Project_V1I1") (part "RC0805FR-07100KL"))
    )
    (comp (ref "R38")
      (value "1M")
      (footprint "R0805")
      (description "Res Thick Film 0805 1M Ohm 1% 0.125W(1/8W) ±100ppm/C Epoxy SMD T/R")
      (fields
        (field (name "MANUFACTURER") "Yageo Phycomp")
        (field (name "MANUFACTURER PART NUMBER") "RC0805FR-071ML")
      )
      (libsource (lib "Bitcoiner_EB_Project_V1I1") (part "RC0805FR-071ML"))
    )
    (comp (ref "R39")
      (value "2.2k")
      (footprint "R0805")
      (description "RESISTOR, THICK FILM, 2.2KOHM, 125mW, 1%, FULL REEL")
      (fields
        (field (name "MANUFACTURER") "Yageo")
        (field (name "MANUFACTURER PART NUMBER") "RC0805FR-072K2L")
      )
      (libsource (lib "Bitcoiner_EB_Project_V1I1") (part "RC0805FR-072K2L"))
    )
    (comp (ref "R40")
      (value "2.2k")
      (footprint "R0805")
      (description "RESISTOR, THICK FILM, 2.2KOHM, 125mW, 1%, FULL REEL")
      (fields
        (field (name "MANUFACTURER") "Yageo")
        (field (name "MANUFACTURER PART NUMBER") "RC0805FR-072K2L")
      )
      (libsource (lib "Bitcoiner_EB_Project_V1I1") (part "RC0805FR-072K2L"))
    )
    (comp (ref "R41")
      (value "470R")
      (footprint "R0805")
      (description "Res Thick Film 0805 470 Ohm 1% 1/8W +/-100ppm/ßC Molded SMD Paper T/R")
      (fields
        (field (name "MANUFACTURER") "Yageo")
        (field (name "MANUFACTURER PART NUMBER") "RC0805FR-07470RL")
      )
      (libsource (lib "Bitcoiner_EB_Project_V1I1") (part "RC0805FR-07470RL"))
    )
    (comp (ref "R42")
      (value "52.3k")
      (footprint "R0805")
      (description "Res Thick Film 0805 52.3K Ohm 1% 1/8W ±100ppm/°C Molded SMD SMD Paper Tape on Plastic Reel")
      (fields
        (field (name "MANUFACTURER") "Bourns")
        (field (name "MANUFACTURER PART NUMBER") "CR0805-FX-5232ELF")
      )
      (libsource (lib "Bitcoiner_EB_Project_V1I1") (part "CR0805-FX-5232ELF"))
    )
    (comp (ref "R43")
      (value "10k")
      (footprint "R0805")
      (description "RES SMD 10K OHM 1% 1/8W 0805")
      (fields
        (field (name "MANUFACTURER") "Yageo")
        (field (name "MANUFACTURER PART NUMBER") "RC0805FR-0710KL")
      )
      (libsource (lib "Bitcoiner_EB_Project_V1I1") (part "RC0805FR-0710KL"))
    )
    (comp (ref "R44")
      (value "0R")
      (footprint "R0805")
      (description "Res Thick Film 0805 0 Ohm Epoxy Pad SMD T/R")
      (fields
        (field (name "MANUFACTURER") "Yageo")
        (field (name "MANUFACTURER PART NUMBER") "RC0805FR-070RL")
      )
      (libsource (lib "Bitcoiner_EB_Project_V1I1") (part "RC0805FR-070RL"))
    )
    (comp (ref "R45")
      (value "0R")
      (footprint "R0805")
      (description "Res Thick Film 0805 0 Ohm Epoxy Pad SMD T/R")
      (fields
        (field (name "MANUFACTURER") "Yageo")
        (field (name "MANUFACTURER PART NUMBER") "RC0805FR-070RL")
      )
      (libsource (lib "Bitcoiner_EB_Project_V1I1") (part "RC0805FR-070RL"))
    )
    (comp (ref "R46")
      (value "0ZCM0012FF2G")
      (footprint "0ZCM0012FF2G")
      (description "PTC RESET FUSE 9V 120MA 0603")
      (fields (field (name "MANUFACTURER") "Bel"))
      (libsource (lib "Bitcoiner_EB_Project_V1I1") (part "0ZCM0012FF2G"))
    )
    (comp (ref "R47")
      (value "200R")
      (footprint "R0603")
      (description "RES SMD 200 OHM 1% 1/10W 0603")
      (fields
        (field (name "MANUFACTURER") "Panasonic")
        (field (name "MANUFACTURER PART NUMBER") "ERJ-3EKF2000V")
      )
      (libsource (lib "Bitcoiner_EB_Project_V1I1") (part "ERJ-3EKF2000V"))
    )
    (comp (ref "R48")
      (value "200R")
      (footprint "R0603")
      (description "RES SMD 200 OHM 1% 1/10W 0603")
      (fields
        (field (name "MANUFACTURER") "Panasonic")
        (field (name "MANUFACTURER PART NUMBER") "ERJ-3EKF2000V")
      )
      (libsource (lib "Bitcoiner_EB_Project_V1I1") (part "ERJ-3EKF2000V"))
    )
    (comp (ref "R49")
      (value "200R")
      (footprint "R0603")
      (description "RES SMD 200 OHM 1% 1/10W 0603")
      (fields
        (field (name "MANUFACTURER") "Panasonic")
        (field (name "MANUFACTURER PART NUMBER") "ERJ-3EKF2000V")
      )
      (libsource (lib "Bitcoiner_EB_Project_V1I1") (part "ERJ-3EKF2000V"))
    )
    (comp (ref "R50")
      (value "200R")
      (footprint "R0603")
      (description "RES SMD 200 OHM 1% 1/10W 0603")
      (fields
        (field (name "MANUFACTURER") "Panasonic")
        (field (name "MANUFACTURER PART NUMBER") "ERJ-3EKF2000V")
      )
      (libsource (lib "Bitcoiner_EB_Project_V1I1") (part "ERJ-3EKF2000V"))
    )
    (comp (ref "R51")
      (value "200R")
      (footprint "R0603")
      (description "RES SMD 200 OHM 1% 1/10W 0603")
      (fields
        (field (name "MANUFACTURER") "Panasonic")
        (field (name "MANUFACTURER PART NUMBER") "ERJ-3EKF2000V")
      )
      (libsource (lib "Bitcoiner_EB_Project_V1I1") (part "ERJ-3EKF2000V"))
    )
    (comp (ref "R52")
      (value "200R")
      (footprint "R0603")
      (description "RES SMD 200 OHM 1% 1/10W 0603")
      (fields
        (field (name "MANUFACTURER") "Panasonic")
        (field (name "MANUFACTURER PART NUMBER") "ERJ-3EKF2000V")
      )
      (libsource (lib "Bitcoiner_EB_Project_V1I1") (part "ERJ-3EKF2000V"))
    )
    (comp (ref "R53")
      (value "200R")
      (footprint "R0603")
      (description "RES SMD 200 OHM 1% 1/10W 0603")
      (fields
        (field (name "MANUFACTURER") "Panasonic")
        (field (name "MANUFACTURER PART NUMBER") "ERJ-3EKF2000V")
      )
      (libsource (lib "Bitcoiner_EB_Project_V1I1") (part "ERJ-3EKF2000V"))
    )
    (comp (ref "R54")
      (value "200R")
      (footprint "R0603")
      (description "RES SMD 200 OHM 1% 1/10W 0603")
      (fields
        (field (name "MANUFACTURER") "Panasonic")
        (field (name "MANUFACTURER PART NUMBER") "ERJ-3EKF2000V")
      )
      (libsource (lib "Bitcoiner_EB_Project_V1I1") (part "ERJ-3EKF2000V"))
    )
    (comp (ref "R55")
      (value "200R")
      (footprint "R0603")
      (description "RES SMD 200 OHM 1% 1/10W 0603")
      (fields
        (field (name "MANUFACTURER") "Panasonic")
        (field (name "MANUFACTURER PART NUMBER") "ERJ-3EKF2000V")
      )
      (libsource (lib "Bitcoiner_EB_Project_V1I1") (part "ERJ-3EKF2000V"))
    )
    (comp (ref "R56")
      (value "200R")
      (footprint "R0603")
      (description "RES SMD 200 OHM 1% 1/10W 0603")
      (fields
        (field (name "MANUFACTURER") "Panasonic")
        (field (name "MANUFACTURER PART NUMBER") "ERJ-3EKF2000V")
      )
      (libsource (lib "Bitcoiner_EB_Project_V1I1") (part "ERJ-3EKF2000V"))
    )
    (comp (ref "R57")
      (value "200R")
      (footprint "R0603")
      (description "RES SMD 200 OHM 1% 1/10W 0603")
      (fields
        (field (name "MANUFACTURER") "Panasonic")
        (field (name "MANUFACTURER PART NUMBER") "ERJ-3EKF2000V")
      )
      (libsource (lib "Bitcoiner_EB_Project_V1I1") (part "ERJ-3EKF2000V"))
    )
    (comp (ref "R58")
      (value "200R")
      (footprint "R0603")
      (description "RES SMD 200 OHM 1% 1/10W 0603")
      (fields
        (field (name "MANUFACTURER") "Panasonic")
        (field (name "MANUFACTURER PART NUMBER") "ERJ-3EKF2000V")
      )
      (libsource (lib "Bitcoiner_EB_Project_V1I1") (part "ERJ-3EKF2000V"))
    )
    (comp (ref "R59")
      (value "200R")
      (footprint "R0603")
      (description "RES SMD 200 OHM 1% 1/10W 0603")
      (fields
        (field (name "MANUFACTURER") "Panasonic")
        (field (name "MANUFACTURER PART NUMBER") "ERJ-3EKF2000V")
      )
      (libsource (lib "Bitcoiner_EB_Project_V1I1") (part "ERJ-3EKF2000V"))
    )
    (comp (ref "R60")
      (value "200R")
      (footprint "R0603")
      (description "RES SMD 200 OHM 1% 1/10W 0603")
      (fields
        (field (name "MANUFACTURER") "Panasonic")
        (field (name "MANUFACTURER PART NUMBER") "ERJ-3EKF2000V")
      )
      (libsource (lib "Bitcoiner_EB_Project_V1I1") (part "ERJ-3EKF2000V"))
    )
    (comp (ref "R61")
      (value "200R")
      (footprint "R0603")
      (description "RES SMD 200 OHM 1% 1/10W 0603")
      (fields
        (field (name "MANUFACTURER") "Panasonic")
        (field (name "MANUFACTURER PART NUMBER") "ERJ-3EKF2000V")
      )
      (libsource (lib "Bitcoiner_EB_Project_V1I1") (part "ERJ-3EKF2000V"))
    )
    (comp (ref "R62")
      (value "200R")
      (footprint "R0603")
      (description "RES SMD 200 OHM 1% 1/10W 0603")
      (fields
        (field (name "MANUFACTURER") "Panasonic")
        (field (name "MANUFACTURER PART NUMBER") "ERJ-3EKF2000V")
      )
      (libsource (lib "Bitcoiner_EB_Project_V1I1") (part "ERJ-3EKF2000V"))
    )
    (comp (ref "SW1")
      (value "OS102011MS2QN1")
      (footprint "OS102011MS2QN1")
      (description "Slide")
      (fields (field (name "MANUFACTURER") "ITT C&K"))
      (libsource (lib "Bitcoiner_EB_Project_V1I1") (part "OS102011MS2QN1"))
    )
    (comp (ref "SW2")
      (value "OS102011MS2QN1")
      (footprint "OS102011MS2QN1")
      (description "Slide")
      (fields (field (name "MANUFACTURER") "ITT C&K"))
      (libsource (lib "Bitcoiner_EB_Project_V1I1") (part "OS102011MS2QN1"))
    )
    (comp (ref "SW3")
      (value "OS102011MS2QN1")
      (footprint "OS102011MS2QN1")
      (description "Slide")
      (fields (field (name "MANUFACTURER") "ITT C&K"))
      (libsource (lib "Bitcoiner_EB_Project_V1I1") (part "OS102011MS2QN1"))
    )
    (comp (ref "SW4")
      (value "OS102011MS2QN1")
      (footprint "OS102011MS2QN1")
      (description "Slide")
      (fields (field (name "MANUFACTURER") "ITT C&K"))
      (libsource (lib "Bitcoiner_EB_Project_V1I1") (part "OS102011MS2QN1"))
    )
    (comp (ref "U1")
      (value "FT2232HL-REEL")
      (footprint "QFP50P1200X1200X160-64N")
      (description "Integrated Circuit")
      (fields (field (name "MOUSER2 PART NUMBER") "895-FT2232HL") (field (name "MANUFACTURER") "FTDI Chip"))
      (libsource (lib "Bitcoiner_EB_Project_V1I1") (part "FT2232HL-REEL"))
    )
    (comp (ref "U2")
      (value "MCP1825ST-3302E/DB")
      (footprint "SOT-223-3")
      (description "IC REG LIN 3.3V 500MA SOT223-3")
      (fields (field (name "MANUFACTURER") "Microchip"))
      (libsource (lib "Bitcoiner_EB_Project_V1I1") (part "MCP1825ST-3302E/DB"))
    )
    (comp (ref "U3")
      (value "93LC56BT-I/OT")
      (footprint "SOT-23-6")
      (description "MICROCHIP - 93LC56BT-I/OT. - 2K, 128 X 16, SERIAL EE, IND ROHS COMPLIANT: YES")
      (fields (field (name "MANUFACTURER") "Microchip"))
      (libsource (lib "Bitcoiner_EB_Project_V1I1") (part "93LC56BT-I/OT"))
    )
    (comp (ref "U4")
      (value "LSF0102DPH")
      (footprint "SOT505-2")
      (fields (field (name "MANUFACTURER") "Nexperia"))
      (libsource (lib "Bitcoiner_EB_Project_V1I1") (part "LSF0102DPH"))
    )
    (comp (ref "U5")
      (value "74LVC1G07GW,125")
      (footprint "SOT353-1")
      (description "NEXPERIA - 74LVC1G07GW,125 - BUFFER, NON-INVERTING, TSSOP-5")
      (fields (field (name "MANUFACTURER") "Nexperia"))
      (libsource (lib "Bitcoiner_EB_Project_V1I1") (part "74LVC1G07GW,125"))
    )
    (comp (ref "U6")
      (value "TPS562202SDRLR")
      (footprint "SOT563-6")
      (fields (field (name "MANUFACTURER") "Texas Instruments"))
      (libsource (lib "Bitcoiner_EB_Project_V1I1") (part "TPS562202SDRLR"))
    )
    (comp (ref "U7")
      (value "MCP1825ST-3302E/DB")
      (footprint "SOT-223-3")
      (description "IC REG LIN 3.3V 500MA SOT223-3")
      (fields (field (name "MANUFACTURER") "Microchip"))
      (libsource (lib "Bitcoiner_EB_Project_V1I1") (part "MCP1825ST-3302E/DB"))
    )
    (comp (ref "Y1")
      (value "ABLS7M2-12.000MHZ-D2Y-T")
      (footprint "ABLS7M2-12.000MHZ-D2Y-T")
      (description "CRYSTAL 12.0000MHZ 18PF SMD")
      (fields
        (field (name "MANUFACTURER") "Abracon")
        (field (name "MANUFACTURER PART NUMBER") "ABLS7M2-12.000MHZ-D-2Y-T")
      )
      (libsource (lib "Bitcoiner_EB_Project_V1I1") (part "ABLS7M2-12.000MHZ-D-2Y-T"))
    )
  )
  (nets
    (net (code "1") (name "+1V8_USB") (class "Default")
      (node (ref "C13") (pin "1") (pinfunction "1_1") (pintype "passive"))
      (node (ref "C18") (pin "2") (pinfunction "2_2") (pintype "passive"))
      (node (ref "C19") (pin "2") (pinfunction "2_2") (pintype "passive"))
      (node (ref "C20") (pin "2") (pinfunction "2_2") (pintype "passive"))
      (node (ref "C28") (pin "2") (pinfunction "2_2") (pintype "passive"))
      (node (ref "U1") (pin "12") (pinfunction "VCORE_1_12") (pintype "passive"))
      (node (ref "U1") (pin "37") (pinfunction "VCORE_2_37") (pintype "passive"))
      (node (ref "U1") (pin "49") (pinfunction "VREGOUT_49") (pintype "passive"))
      (node (ref "U1") (pin "64") (pinfunction "VCORE_3_64") (pintype "passive"))
    )
    (net (code "2") (name "+3V3") (class "Default")
      (node (ref "C10") (pin "2") (pinfunction "2_2") (pintype "passive"))
      (node (ref "C14") (pin "2") (pinfunction "2_2") (pintype "passive"))
      (node (ref "J2") (pin "11") (pinfunction "11_11") (pintype "passive"))
      (node (ref "J2") (pin "12") (pinfunction "12_12") (pintype "passive"))
      (node (ref "J5") (pin "11") (pinfunction "11_11") (pintype "passive"))
      (node (ref "J5") (pin "12") (pinfunction "12_12") (pintype "passive"))
      (node (ref "Q1") (pin "1") (pinfunction "1_1") (pintype "passive"))
      (node (ref "Q1") (pin "4") (pinfunction "4_4") (pintype "passive"))
      (node (ref "R15") (pin "2") (pinfunction "2_2") (pintype "passive"))
      (node (ref "R16") (pin "2") (pinfunction "2_2") (pintype "passive"))
      (node (ref "R21") (pin "2") (pinfunction "2_2") (pintype "passive"))
      (node (ref "R23") (pin "2") (pinfunction "2_2") (pintype "passive"))
      (node (ref "R24") (pin "2") (pinfunction "2_2") (pintype "passive"))
      (node (ref "R25") (pin "2") (pinfunction "2_2") (pintype "passive"))
      (node (ref "R26") (pin "2") (pinfunction "2_2") (pintype "passive"))
      (node (ref "R27") (pin "2") (pinfunction "2_2") (pintype "passive"))
      (node (ref "R28") (pin "2") (pinfunction "2_2") (pintype "passive"))
      (node (ref "R29") (pin "2") (pinfunction "2_2") (pintype "passive"))
      (node (ref "R30") (pin "2") (pinfunction "2_2") (pintype "passive"))
      (node (ref "R36") (pin "2") (pinfunction "2_2") (pintype "passive"))
      (node (ref "R41") (pin "2") (pinfunction "2_2") (pintype "passive"))
      (node (ref "SW1") (pin "1") (pinfunction "1_1") (pintype "passive"))
      (node (ref "SW2") (pin "1") (pinfunction "1_1") (pintype "passive"))
      (node (ref "SW3") (pin "1") (pinfunction "1_1") (pintype "passive"))
      (node (ref "SW4") (pin "1") (pinfunction "1_1") (pintype "passive"))
      (node (ref "U4") (pin "2") (pinfunction "REFA_2") (pintype "passive"))
      (node (ref "U5") (pin "5") (pinfunction "5_5") (pintype "passive"))
      (node (ref "U7") (pin "3") (pinfunction "OUT_3") (pintype "passive"))
    )
    (net (code "3") (name "+3V3_USB") (class "Default")
      (node (ref "C15") (pin "2") (pinfunction "2_2") (pintype "passive"))
      (node (ref "C21") (pin "2") (pinfunction "2_2") (pintype "passive"))
      (node (ref "C22") (pin "2") (pinfunction "2_2") (pintype "passive"))
      (node (ref "C23") (pin "2") (pinfunction "2_2") (pintype "passive"))
      (node (ref "C24") (pin "2") (pinfunction "2_2") (pintype "passive"))
      (node (ref "C25") (pin "2") (pinfunction "2_2") (pintype "passive"))
      (node (ref "C6") (pin "2") (pinfunction "2_2") (pintype "passive"))
      (node (ref "FB1") (pin "1") (pinfunction "1_1") (pintype "passive"))
      (node (ref "FB2") (pin "1") (pinfunction "1_1") (pintype "passive"))
      (node (ref "R3") (pin "2") (pinfunction "2_2") (pintype "passive"))
      (node (ref "R4") (pin "2") (pinfunction "2_2") (pintype "passive"))
      (node (ref "R5") (pin "2") (pinfunction "2_2") (pintype "passive"))
      (node (ref "R6") (pin "2") (pinfunction "2_2") (pintype "passive"))
      (node (ref "R7") (pin "2") (pinfunction "2_2") (pintype "passive"))
      (node (ref "R8") (pin "2") (pinfunction "2_2") (pintype "passive"))
      (node (ref "U1") (pin "20") (pinfunction "VCCIO_1_20") (pintype "passive"))
      (node (ref "U1") (pin "31") (pinfunction "VCCIO_2_31") (pintype "passive"))
      (node (ref "U1") (pin "42") (pinfunction "VCCIO_3_42") (pintype "passive"))
      (node (ref "U1") (pin "50") (pinfunction "VREGIN_50") (pintype "passive"))
      (node (ref "U1") (pin "56") (pinfunction "VCCIO_4_56") (pintype "passive"))
      (node (ref "U2") (pin "3") (pinfunction "OUT_3") (pintype "passive"))
      (node (ref "U3") (pin "6") (pinfunction "VCC_6") (pintype "passive"))
    )
    (net (code "4") (name "+5V") (class "Default")
      (node (ref "C33") (pin "1") (pinfunction "1_1") (pintype "passive"))
      (node (ref "C9") (pin "2") (pinfunction "2_2") (pintype "passive"))
      (node (ref "J11") (pin "2") (pinfunction "2_2") (pintype "passive"))
      (node (ref "R17") (pin "2") (pinfunction "2_2") (pintype "passive"))
      (node (ref "R18") (pin "2") (pinfunction "2_2") (pintype "passive"))
      (node (ref "R19") (pin "2") (pinfunction "2_2") (pintype "passive"))
      (node (ref "R45") (pin "2") (pinfunction "2_2") (pintype "passive"))
      (node (ref "R46") (pin "2") (pinfunction "2_2") (pintype "passive"))
      (node (ref "U7") (pin "1") (pinfunction "IN_1") (pintype "passive"))
    )
    (net (code "5") (name "+5V_DC_JACK") (class "Default")
      (node (ref "C31") (pin "2") (pinfunction "2_2") (pintype "passive"))
      (node (ref "C32") (pin "2") (pinfunction "2_2") (pintype "passive"))
      (node (ref "J11") (pin "3") (pinfunction "3_3") (pintype "passive"))
      (node (ref "L1") (pin "2") (pinfunction "2_2") (pintype "passive"))
      (node (ref "R42") (pin "2") (pinfunction "2_2") (pintype "passive"))
    )
    (net (code "6") (name "+5V_USB") (class "Default")
      (node (ref "C1") (pin "1") (pinfunction "1_1") (pintype "passive"))
      (node (ref "C27") (pin "2") (pinfunction "2_2") (pintype "passive"))
      (node (ref "FB3") (pin "2") (pinfunction "2_2") (pintype "passive"))
      (node (ref "U2") (pin "1") (pinfunction "IN_1") (pintype "passive"))
    )
    (net (code "7") (name "+5V_USB_UNFILTERED") (class "Default")
      (node (ref "C26") (pin "2") (pinfunction "2_2") (pintype "passive"))
      (node (ref "FB3") (pin "1") (pinfunction "1_1") (pintype "passive"))
      (node (ref "J11") (pin "1") (pinfunction "1_1") (pintype "passive"))
      (node (ref "J4") (pin "1") (pinfunction "V_1") (pintype "passive"))
    )
    (net (code "8") (name "+12V") (class "Default")
      (node (ref "C17") (pin "2") (pinfunction "2_2") (pintype "passive"))
      (node (ref "C29") (pin "2") (pinfunction "2_2") (pintype "passive"))
      (node (ref "C30") (pin "2") (pinfunction "2_2") (pintype "passive"))
      (node (ref "J10") (pin "1") (pinfunction "1_1") (pintype "passive"))
      (node (ref "R44") (pin "1") (pinfunction "1_1") (pintype "passive"))
      (node (ref "U6") (pin "1") (pinfunction "VIN_1") (pintype "passive"))
      (node (ref "U6") (pin "5") (pinfunction "EN_5") (pintype "passive"))
    )
    (net (code "9") (name "+VZynq") (class "Default")
      (node (ref "J3") (pin "1") (pinfunction "1_1") (pintype "passive"))
      (node (ref "J3") (pin "2") (pinfunction "2_2") (pintype "passive"))
      (node (ref "J6") (pin "1") (pinfunction "1_1") (pintype "passive"))
      (node (ref "J6") (pin "2") (pinfunction "2_2") (pintype "passive"))
      (node (ref "J8") (pin "1") (pinfunction "1_1") (pintype "passive"))
      (node (ref "J8") (pin "2") (pinfunction "2_2") (pintype "passive"))
      (node (ref "R44") (pin "2") (pinfunction "2_2") (pintype "passive"))
      (node (ref "R45") (pin "1") (pinfunction "1_1") (pintype "passive"))
    )
    (net (code "10") (name "/ACBUS5{slash}~{SRST}") (class "Default")
      (node (ref "J1") (pin "6") (pinfunction "6_6") (pintype "passive"))
      (node (ref "U1") (pin "32") (pinfunction "ACBUS5_32") (pintype "passive"))
    )
    (net (code "11") (name "/ADBUS0{slash}TCK") (class "Default")
      (node (ref "J1") (pin "2") (pinfunction "2_2") (pintype "passive"))
      (node (ref "U1") (pin "16") (pinfunction "ADBUS0_16") (pintype "passive"))
    )
    (net (code "12") (name "/ADBUS1{slash}TDI") (class "Default")
      (node (ref "J1") (pin "3") (pinfunction "3_3") (pintype "passive"))
      (node (ref "U1") (pin "17") (pinfunction "ADBUS1_17") (pintype "passive"))
    )
    (net (code "13") (name "/ADBUS2{slash}TDO") (class "Default")
      (node (ref "J1") (pin "4") (pinfunction "4_4") (pintype "passive"))
      (node (ref "U1") (pin "18") (pinfunction "ADBUS2_18") (pintype "passive"))
    )
    (net (code "14") (name "/ADBUS3{slash}TMS") (class "Default")
      (node (ref "J1") (pin "5") (pinfunction "5_5") (pintype "passive"))
      (node (ref "U1") (pin "19") (pinfunction "ADBUS3_19") (pintype "passive"))
    )
    (net (code "15") (name "/AN0") (class "Default")
      (node (ref "J8") (pin "8") (pinfunction "8_8") (pintype "passive"))
      (node (ref "R39") (pin "2") (pinfunction "2_2") (pintype "passive"))
    )
    (net (code "16") (name "/AN1") (class "Default")
      (node (ref "J6") (pin "17") (pinfunction "17_17") (pintype "passive"))
      (node (ref "R40") (pin "2") (pinfunction "2_2") (pintype "passive"))
    )
    (net (code "17") (name "/BDBUS0{slash}CTS") (class "Default")
      (node (ref "J7") (pin "5") (pinfunction "5_5") (pintype "passive"))
      (node (ref "U1") (pin "41") (pinfunction "BDBUS3_41") (pintype "passive"))
    )
    (net (code "18") (name "/BDBUS0{slash}RTS") (class "Default")
      (node (ref "J7") (pin "4") (pinfunction "4_4") (pintype "passive"))
      (node (ref "U1") (pin "40") (pinfunction "BDBUS2_40") (pintype "passive"))
    )
    (net (code "19") (name "/BDBUS0{slash}TXD") (class "Default")
      (node (ref "J7") (pin "2") (pinfunction "2_2") (pintype "passive"))
      (node (ref "U1") (pin "38") (pinfunction "BDBUS0_38") (pintype "passive"))
    )
    (net (code "20") (name "/BDBUS1{slash}RXD") (class "Default")
      (node (ref "J7") (pin "3") (pinfunction "3_3") (pintype "passive"))
      (node (ref "U1") (pin "39") (pinfunction "BDBUS1_39") (pintype "passive"))
    )
    (net (code "21") (name "/BST") (class "Default")
      (node (ref "C16") (pin "2") (pinfunction "2_2") (pintype "passive"))
      (node (ref "U6") (pin "4") (pinfunction "BST_4") (pintype "passive"))
    )
    (net (code "22") (name "/CA") (class "Default")
      (node (ref "J6") (pin "6") (pinfunction "6_6") (pintype "passive"))
      (node (ref "R14") (pin "1") (pinfunction "1_1") (pintype "passive"))
    )
    (net (code "23") (name "/CB") (class "Default")
      (node (ref "J6") (pin "15") (pinfunction "15_15") (pintype "passive"))
      (node (ref "R20") (pin "1") (pinfunction "1_1") (pintype "passive"))
    )
    (net (code "24") (name "/CC") (class "Default")
      (node (ref "J6") (pin "11") (pinfunction "11_11") (pintype "passive"))
      (node (ref "R22") (pin "1") (pinfunction "1_1") (pintype "passive"))
    )
    (net (code "25") (name "/CD") (class "Default")
      (node (ref "J6") (pin "20") (pinfunction "20_20") (pintype "passive"))
      (node (ref "R31") (pin "1") (pinfunction "1_1") (pintype "passive"))
    )
    (net (code "26") (name "/CE") (class "Default")
      (node (ref "J8") (pin "14") (pinfunction "14_14") (pintype "passive"))
      (node (ref "R32") (pin "1") (pinfunction "1_1") (pintype "passive"))
    )
    (net (code "27") (name "/CF") (class "Default")
      (node (ref "J8") (pin "13") (pinfunction "13_13") (pintype "passive"))
      (node (ref "R33") (pin "1") (pinfunction "1_1") (pintype "passive"))
    )
    (net (code "28") (name "/CG") (class "Default")
      (node (ref "J3") (pin "20") (pinfunction "20_20") (pintype "passive"))
      (node (ref "R34") (pin "1") (pinfunction "1_1") (pintype "passive"))
    )
    (net (code "29") (name "/CP") (class "Default")
      (node (ref "J3") (pin "18") (pinfunction "18_18") (pintype "passive"))
      (node (ref "R35") (pin "1") (pinfunction "1_1") (pintype "passive"))
    )
    (net (code "30") (name "/FB") (class "Default")
      (node (ref "R42") (pin "1") (pinfunction "1_1") (pintype "passive"))
      (node (ref "R43") (pin "2") (pinfunction "2_2") (pintype "passive"))
      (node (ref "U6") (pin "6") (pinfunction "FB_6") (pintype "passive"))
    )
    (net (code "31") (name "/HDMI_CEC") (class "Default")
      (node (ref "D1") (pin "1") (pinfunction "Cathode_1") (pintype "passive"))
      (node (ref "J3") (pin "6") (pinfunction "6_6") (pintype "passive"))
      (node (ref "J9") (pin "13") (pinfunction "CEC_13") (pintype "passive"))
    )
    (net (code "32") (name "/HDMI_CLK_N") (class "Default")
      (node (ref "J3") (pin "17") (pinfunction "17_17") (pintype "passive"))
      (node (ref "J9") (pin "12") (pinfunction "CLK-_12") (pintype "passive"))
      (node (ref "R30") (pin "1") (pinfunction "1_1") (pintype "passive"))
    )
    (net (code "33") (name "/HDMI_CLK_P") (class "Default")
      (node (ref "J3") (pin "19") (pinfunction "19_19") (pintype "passive"))
      (node (ref "J9") (pin "10") (pinfunction "CLK+_10") (pintype "passive"))
      (node (ref "R29") (pin "1") (pinfunction "1_1") (pintype "passive"))
    )
    (net (code "34") (name "/HDMI_D0_N") (class "Default")
      (node (ref "J3") (pin "13") (pinfunction "13_13") (pintype "passive"))
      (node (ref "J9") (pin "9") (pinfunction "D0-_9") (pintype "passive"))
      (node (ref "R28") (pin "1") (pinfunction "1_1") (pintype "passive"))
    )
    (net (code "35") (name "/HDMI_D0_P") (class "Default")
      (node (ref "J3") (pin "16") (pinfunction "16_16") (pintype "passive"))
      (node (ref "J9") (pin "7") (pinfunction "D0+_7") (pintype "passive"))
      (node (ref "R27") (pin "1") (pinfunction "1_1") (pintype "passive"))
    )
    (net (code "36") (name "/HDMI_D1_N") (class "Default")
      (node (ref "J3") (pin "8") (pinfunction "8_8") (pintype "passive"))
      (node (ref "J9") (pin "6") (pinfunction "D1-_6") (pintype "passive"))
      (node (ref "R26") (pin "1") (pinfunction "1_1") (pintype "passive"))
    )
    (net (code "37") (name "/HDMI_D1_P") (class "Default")
      (node (ref "J3") (pin "9") (pinfunction "9_9") (pintype "passive"))
      (node (ref "J9") (pin "4") (pinfunction "D1+_4") (pintype "passive"))
      (node (ref "R25") (pin "1") (pinfunction "1_1") (pintype "passive"))
    )
    (net (code "38") (name "/HDMI_D2_N") (class "Default")
      (node (ref "J3") (pin "5") (pinfunction "5_5") (pintype "passive"))
      (node (ref "J9") (pin "3") (pinfunction "D2-_3") (pintype "passive"))
      (node (ref "R24") (pin "1") (pinfunction "1_1") (pintype "passive"))
    )
    (net (code "39") (name "/HDMI_D2_P") (class "Default")
      (node (ref "J3") (pin "7") (pinfunction "7_7") (pintype "passive"))
      (node (ref "J9") (pin "1") (pinfunction "D2+_1") (pintype "passive"))
      (node (ref "R23") (pin "1") (pinfunction "1_1") (pintype "passive"))
    )
    (net (code "40") (name "/HDMI_HPD") (class "Default")
      (node (ref "J3") (pin "15") (pinfunction "15_15") (pintype "passive"))
      (node (ref "R36") (pin "1") (pinfunction "1_1") (pintype "passive"))
      (node (ref "U5") (pin "4") (pinfunction "4_4") (pintype "passive"))
    )
    (net (code "41") (name "/HDMI_HPD_LS") (class "Default")
      (node (ref "J9") (pin "19") (pinfunction "HPA_19") (pintype "passive"))
      (node (ref "R37") (pin "2") (pinfunction "2_2") (pintype "passive"))
      (node (ref "U5") (pin "2") (pinfunction "2_2") (pintype "passive"))
    )
    (net (code "42") (name "/HDMI_SCL") (class "Default")
      (node (ref "J3") (pin "11") (pinfunction "11_11") (pintype "passive"))
      (node (ref "R15") (pin "1") (pinfunction "1_1") (pintype "passive"))
      (node (ref "U4") (pin "3") (pinfunction "A1_3") (pintype "passive"))
    )
    (net (code "43") (name "/HDMI_SCL_LS") (class "Default")
      (node (ref "J9") (pin "15") (pinfunction "SCL_15") (pintype "passive"))
      (node (ref "R18") (pin "1") (pinfunction "1_1") (pintype "passive"))
      (node (ref "U4") (pin "6") (pinfunction "B1_6") (pintype "passive"))
    )
    (net (code "44") (name "/HDMI_SDA") (class "Default")
      (node (ref "J3") (pin "14") (pinfunction "14_14") (pintype "passive"))
      (node (ref "R16") (pin "1") (pinfunction "1_1") (pintype "passive"))
      (node (ref "U4") (pin "4") (pinfunction "A2_4") (pintype "passive"))
    )
    (net (code "45") (name "/HDMI_SDA_LS") (class "Default")
      (node (ref "J9") (pin "16") (pinfunction "SDA_16") (pintype "passive"))
      (node (ref "R19") (pin "1") (pinfunction "1_1") (pintype "passive"))
      (node (ref "U4") (pin "5") (pinfunction "B2_5") (pintype "passive"))
    )
    (net (code "46") (name "/HDMI_SHIELD") (class "Default")
      (node (ref "C11") (pin "2") (pinfunction "2_2") (pintype "passive"))
      (node (ref "J9") (pin "20") (pinfunction "S1_20") (pintype "passive"))
      (node (ref "J9") (pin "21") (pinfunction "S2_21") (pintype "passive"))
      (node (ref "J9") (pin "22") (pinfunction "S3_22") (pintype "passive"))
      (node (ref "J9") (pin "23") (pinfunction "S4_23") (pintype "passive"))
      (node (ref "R38") (pin "2") (pinfunction "2_2") (pintype "passive"))
    )
    (net (code "47") (name "/JA1_N") (class "Default")
      (node (ref "J6") (pin "5") (pinfunction "5_5") (pintype "passive"))
      (node (ref "R49") (pin "1") (pinfunction "1_1") (pintype "passive"))
    )
    (net (code "48") (name "/JA1_P") (class "Default")
      (node (ref "J6") (pin "7") (pinfunction "7_7") (pintype "passive"))
      (node (ref "R47") (pin "1") (pinfunction "1_1") (pintype "passive"))
    )
    (net (code "49") (name "/JA2_N") (class "Default")
      (node (ref "J6") (pin "8") (pinfunction "8_8") (pintype "passive"))
      (node (ref "R53") (pin "1") (pinfunction "1_1") (pintype "passive"))
    )
    (net (code "50") (name "/JA2_P") (class "Default")
      (node (ref "J6") (pin "14") (pinfunction "14_14") (pintype "passive"))
      (node (ref "R51") (pin "1") (pinfunction "1_1") (pintype "passive"))
    )
    (net (code "51") (name "/JA3_N") (class "Default")
      (node (ref "J6") (pin "9") (pinfunction "9_9") (pintype "passive"))
      (node (ref "R50") (pin "2") (pinfunction "2_2") (pintype "passive"))
    )
    (net (code "52") (name "/JA3_P") (class "Default")
      (node (ref "J6") (pin "13") (pinfunction "13_13") (pintype "passive"))
      (node (ref "R48") (pin "2") (pinfunction "2_2") (pintype "passive"))
    )
    (net (code "53") (name "/JA4_N") (class "Default")
      (node (ref "J6") (pin "18") (pinfunction "18_18") (pintype "passive"))
      (node (ref "R54") (pin "2") (pinfunction "2_2") (pintype "passive"))
    )
    (net (code "54") (name "/JA4_P") (class "Default")
      (node (ref "J6") (pin "16") (pinfunction "16_16") (pintype "passive"))
      (node (ref "R52") (pin "2") (pinfunction "2_2") (pintype "passive"))
    )
    (net (code "55") (name "/JB1_N") (class "Default")
      (node (ref "J6") (pin "19") (pinfunction "19_19") (pintype "passive"))
      (node (ref "R57") (pin "1") (pinfunction "1_1") (pintype "passive"))
    )
    (net (code "56") (name "/JB1_P") (class "Default")
      (node (ref "J8") (pin "5") (pinfunction "5_5") (pintype "passive"))
      (node (ref "R55") (pin "1") (pinfunction "1_1") (pintype "passive"))
    )
    (net (code "57") (name "/JB2_N") (class "Default")
      (node (ref "J8") (pin "11") (pinfunction "11_11") (pintype "passive"))
      (node (ref "R61") (pin "1") (pinfunction "1_1") (pintype "passive"))
    )
    (net (code "58") (name "/JB2_P") (class "Default")
      (node (ref "J8") (pin "6") (pinfunction "6_6") (pintype "passive"))
      (node (ref "R59") (pin "1") (pinfunction "1_1") (pintype "passive"))
    )
    (net (code "59") (name "/JB3_N") (class "Default")
      (node (ref "J8") (pin "7") (pinfunction "7_7") (pintype "passive"))
      (node (ref "R58") (pin "2") (pinfunction "2_2") (pintype "passive"))
    )
    (net (code "60") (name "/JB3_P") (class "Default")
      (node (ref "J8") (pin "9") (pinfunction "9_9") (pintype "passive"))
      (node (ref "R56") (pin "2") (pinfunction "2_2") (pintype "passive"))
    )
    (net (code "61") (name "/JB4_N") (class "Default")
      (node (ref "J8") (pin "17") (pinfunction "17_17") (pintype "passive"))
      (node (ref "R62") (pin "2") (pinfunction "2_2") (pintype "passive"))
    )
    (net (code "62") (name "/JB4_P") (class "Default")
      (node (ref "J8") (pin "16") (pinfunction "16_16") (pintype "passive"))
      (node (ref "R60") (pin "2") (pinfunction "2_2") (pintype "passive"))
    )
    (net (code "63") (name "/RX_LED") (class "Default")
      (node (ref "LED1") (pin "1") (pinfunction "Cathode_1") (pintype "passive"))
      (node (ref "U1") (pin "54") (pinfunction "BCBUS3_54") (pintype "passive"))
    )
    (net (code "64") (name "/SW") (class "Default")
      (node (ref "C16") (pin "1") (pinfunction "1_1") (pintype "passive"))
      (node (ref "L1") (pin "1") (pinfunction "1_1") (pintype "passive"))
      (node (ref "U6") (pin "2") (pinfunction "SW_2") (pintype "passive"))
    )
    (net (code "65") (name "/SW0") (class "Default")
      (node (ref "J8") (pin "15") (pinfunction "15_15") (pintype "passive"))
      (node (ref "R10") (pin "2") (pinfunction "2_2") (pintype "passive"))
    )
    (net (code "66") (name "/SW1") (class "Default")
      (node (ref "J8") (pin "18") (pinfunction "18_18") (pintype "passive"))
      (node (ref "R11") (pin "2") (pinfunction "2_2") (pintype "passive"))
    )
    (net (code "67") (name "/SW2") (class "Default")
      (node (ref "J8") (pin "20") (pinfunction "20_20") (pintype "passive"))
      (node (ref "R12") (pin "2") (pinfunction "2_2") (pintype "passive"))
    )
    (net (code "68") (name "/SW3") (class "Default")
      (node (ref "J8") (pin "19") (pinfunction "19_19") (pintype "passive"))
      (node (ref "R13") (pin "2") (pinfunction "2_2") (pintype "passive"))
    )
    (net (code "69") (name "/TX_LED") (class "Default")
      (node (ref "LED2") (pin "1") (pinfunction "Cathode_1") (pintype "passive"))
      (node (ref "U1") (pin "55") (pinfunction "BCBUS4_55") (pintype "passive"))
    )
    (net (code "70") (name "/USB_N") (class "Default")
      (node (ref "J4") (pin "2") (pinfunction "D-_2") (pintype "passive"))
      (node (ref "U1") (pin "7") (pinfunction "DM_7") (pintype "passive"))
    )
    (net (code "71") (name "/USB_P") (class "Default")
      (node (ref "J4") (pin "3") (pinfunction "D+_3") (pintype "passive"))
      (node (ref "U1") (pin "8") (pinfunction "DP_8") (pintype "passive"))
    )
    (net (code "72") (name "GND") (class "Default")
      (node (ref "C1") (pin "2") (pinfunction "2_2") (pintype "passive"))
      (node (ref "C10") (pin "1") (pinfunction "1_1") (pintype "passive"))
      (node (ref "C11") (pin "1") (pinfunction "1_1") (pintype "passive"))
      (node (ref "C12") (pin "2") (pinfunction "2_2") (pintype "passive"))
      (node (ref "C13") (pin "2") (pinfunction "2_2") (pintype "passive"))
      (node (ref "C14") (pin "1") (pinfunction "1_1") (pintype "passive"))
      (node (ref "C15") (pin "1") (pinfunction "1_1") (pintype "passive"))
      (node (ref "C17") (pin "1") (pinfunction "1_1") (pintype "passive"))
      (node (ref "C18") (pin "1") (pinfunction "1_1") (pintype "passive"))
      (node (ref "C19") (pin "1") (pinfunction "1_1") (pintype "passive"))
      (node (ref "C2") (pin "1") (pinfunction "1_1") (pintype "passive"))
      (node (ref "C20") (pin "1") (pinfunction "1_1") (pintype "passive"))
      (node (ref "C21") (pin "1") (pinfunction "1_1") (pintype "passive"))
      (node (ref "C22") (pin "1") (pinfunction "1_1") (pintype "passive"))
      (node (ref "C23") (pin "1") (pinfunction "1_1") (pintype "passive"))
      (node (ref "C24") (pin "1") (pinfunction "1_1") (pintype "passive"))
      (node (ref "C25") (pin "1") (pinfunction "1_1") (pintype "passive"))
      (node (ref "C26") (pin "1") (pinfunction "1_1") (pintype "passive"))
      (node (ref "C27") (pin "1") (pinfunction "1_1") (pintype "passive"))
      (node (ref "C28") (pin "1") (pinfunction "1_1") (pintype "passive"))
      (node (ref "C29") (pin "1") (pinfunction "1_1") (pintype "passive"))
      (node (ref "C3") (pin "2") (pinfunction "2_2") (pintype "passive"))
      (node (ref "C30") (pin "1") (pinfunction "1_1") (pintype "passive"))
      (node (ref "C31") (pin "1") (pinfunction "1_1") (pintype "passive"))
      (node (ref "C32") (pin "1") (pinfunction "1_1") (pintype "passive"))
      (node (ref "C33") (pin "2") (pinfunction "2_2") (pintype "passive"))
      (node (ref "C4") (pin "1") (pinfunction "1_1") (pintype "passive"))
      (node (ref "C5") (pin "1") (pinfunction "1_1") (pintype "passive"))
      (node (ref "C6") (pin "1") (pinfunction "1_1") (pintype "passive"))
      (node (ref "C7") (pin "1") (pinfunction "1_1") (pintype "passive"))
      (node (ref "C8") (pin "1") (pinfunction "1_1") (pintype "passive"))
      (node (ref "C9") (pin "1") (pinfunction "1_1") (pintype "passive"))
      (node (ref "J1") (pin "1") (pinfunction "1_1") (pintype "passive"))
      (node (ref "J10") (pin "2") (pinfunction "2_2") (pintype "passive"))
      (node (ref "J10") (pin "3") (pinfunction "3_3") (pintype "passive"))
      (node (ref "J2") (pin "10") (pinfunction "10_10") (pintype "passive"))
      (node (ref "J2") (pin "9") (pinfunction "9_9") (pintype "passive"))
      (node (ref "J3") (pin "12") (pinfunction "12_12") (pintype "passive"))
      (node (ref "J3") (pin "3") (pinfunction "3_3") (pintype "passive"))
      (node (ref "J3") (pin "4") (pinfunction "4_4") (pintype "passive"))
      (node (ref "J4") (pin "5") (pinfunction "G_5") (pintype "passive"))
      (node (ref "J5") (pin "10") (pinfunction "10_10") (pintype "passive"))
      (node (ref "J5") (pin "9") (pinfunction "9_9") (pintype "passive"))
      (node (ref "J6") (pin "12") (pinfunction "12_12") (pintype "passive"))
      (node (ref "J6") (pin "3") (pinfunction "3_3") (pintype "passive"))
      (node (ref "J6") (pin "4") (pinfunction "4_4") (pintype "passive"))
      (node (ref "J7") (pin "1") (pinfunction "1_1") (pintype "passive"))
      (node (ref "J8") (pin "12") (pinfunction "12_12") (pintype "passive"))
      (node (ref "J8") (pin "3") (pinfunction "3_3") (pintype "passive"))
      (node (ref "J8") (pin "4") (pinfunction "4_4") (pintype "passive"))
      (node (ref "J9") (pin "11") (pinfunction "CLKS_11") (pintype "passive"))
      (node (ref "J9") (pin "17") (pinfunction "DDC/CECG_17") (pintype "passive"))
      (node (ref "J9") (pin "2") (pinfunction "D2S_2") (pintype "passive"))
      (node (ref "J9") (pin "5") (pinfunction "D1S_5") (pintype "passive"))
      (node (ref "J9") (pin "8") (pinfunction "D0S_8") (pintype "passive"))
      (node (ref "LED3") (pin "1") (pinfunction "Cathode_1") (pintype "passive"))
      (node (ref "R1") (pin "1") (pinfunction "1_1") (pintype "passive"))
      (node (ref "R2") (pin "1") (pinfunction "1_1") (pintype "passive"))
      (node (ref "R37") (pin "1") (pinfunction "1_1") (pintype "passive"))
      (node (ref "R38") (pin "1") (pinfunction "1_1") (pintype "passive"))
      (node (ref "R43") (pin "1") (pinfunction "1_1") (pintype "passive"))
      (node (ref "SW1") (pin "3") (pinfunction "3_3") (pintype "passive"))
      (node (ref "SW2") (pin "3") (pinfunction "3_3") (pintype "passive"))
      (node (ref "SW3") (pin "3") (pinfunction "3_3") (pintype "passive"))
      (node (ref "SW4") (pin "3") (pinfunction "3_3") (pintype "passive"))
      (node (ref "U1") (pin "1") (pinfunction "GND_1_1") (pintype "passive"))
      (node (ref "U1") (pin "10") (pinfunction "AGND_10") (pintype "passive"))
      (node (ref "U1") (pin "11") (pinfunction "GND_3_11") (pintype "passive"))
      (node (ref "U1") (pin "13") (pinfunction "TEST_13") (pintype "passive"))
      (node (ref "U1") (pin "15") (pinfunction "GND_4_15") (pintype "passive"))
      (node (ref "U1") (pin "25") (pinfunction "GND_5_25") (pintype "passive"))
      (node (ref "U1") (pin "35") (pinfunction "GND_6_35") (pintype "passive"))
      (node (ref "U1") (pin "47") (pinfunction "GND_7_47") (pintype "passive"))
      (node (ref "U1") (pin "5") (pinfunction "GND_2_5") (pintype "passive"))
      (node (ref "U1") (pin "51") (pinfunction "GND_8_51") (pintype "passive"))
      (node (ref "U2") (pin "2") (pinfunction "GND_2") (pintype "passive"))
      (node (ref "U2") (pin "4") (pinfunction "PAD_4") (pintype "passive"))
      (node (ref "U3") (pin "2") (pinfunction "VSS_2") (pintype "passive"))
      (node (ref "U4") (pin "1") (pinfunction "GND_1") (pintype "passive"))
      (node (ref "U5") (pin "3") (pinfunction "3_3") (pintype "passive"))
      (node (ref "U6") (pin "3") (pinfunction "GND_3") (pintype "passive"))
      (node (ref "U7") (pin "2") (pinfunction "GND_2") (pintype "passive"))
      (node (ref "U7") (pin "4") (pinfunction "PAD_4") (pintype "passive"))
    )
    (net (code "73") (name "Net-(D1-Anode)") (class "Default")
      (node (ref "D1") (pin "2") (pinfunction "Anode_2") (pintype "passive"))
      (node (ref "R21") (pin "1") (pinfunction "1_1") (pintype "passive"))
    )
    (net (code "74") (name "Net-(DS1-A1)") (class "Default")
      (node (ref "DS1") (pin "9") (pinfunction "A1_9") (pintype "passive"))
      (node (ref "Q1") (pin "6") (pinfunction "6_6") (pintype "passive"))
    )
    (net (code "75") (name "Net-(DS1-A2)") (class "Default")
      (node (ref "DS1") (pin "6") (pinfunction "A2_6") (pintype "passive"))
      (node (ref "Q1") (pin "3") (pinfunction "3_3") (pintype "passive"))
    )
    (net (code "76") (name "Net-(DS1-CA)") (class "Default")
      (node (ref "DS1") (pin "7") (pinfunction "CA_7") (pintype "passive"))
      (node (ref "R14") (pin "2") (pinfunction "2_2") (pintype "passive"))
    )
    (net (code "77") (name "Net-(DS1-CB)") (class "Default")
      (node (ref "DS1") (pin "8") (pinfunction "CB_8") (pintype "passive"))
      (node (ref "R20") (pin "2") (pinfunction "2_2") (pintype "passive"))
    )
    (net (code "78") (name "Net-(DS1-CC)") (class "Default")
      (node (ref "DS1") (pin "3") (pinfunction "CC_3") (pintype "passive"))
      (node (ref "R22") (pin "2") (pinfunction "2_2") (pintype "passive"))
    )
    (net (code "79") (name "Net-(DS1-CD)") (class "Default")
      (node (ref "DS1") (pin "2") (pinfunction "CD_2") (pintype "passive"))
      (node (ref "R31") (pin "2") (pinfunction "2_2") (pintype "passive"))
    )
    (net (code "80") (name "Net-(DS1-CE)") (class "Default")
      (node (ref "DS1") (pin "1") (pinfunction "CE_1") (pintype "passive"))
      (node (ref "R32") (pin "2") (pinfunction "2_2") (pintype "passive"))
    )
    (net (code "81") (name "Net-(DS1-CF)") (class "Default")
      (node (ref "DS1") (pin "10") (pinfunction "CF_10") (pintype "passive"))
      (node (ref "R33") (pin "2") (pinfunction "2_2") (pintype "passive"))
    )
    (net (code "82") (name "Net-(DS1-CG)") (class "Default")
      (node (ref "DS1") (pin "4") (pinfunction "CG_4") (pintype "passive"))
      (node (ref "R34") (pin "2") (pinfunction "2_2") (pintype "passive"))
    )
    (net (code "83") (name "Net-(DS1-CP)") (class "Default")
      (node (ref "DS1") (pin "5") (pinfunction "CP_5") (pintype "passive"))
      (node (ref "R35") (pin "2") (pinfunction "2_2") (pintype "passive"))
    )
    (net (code "84") (name "Net-(J2-Pad1)") (class "Default")
      (node (ref "J2") (pin "1") (pinfunction "1_1") (pintype "passive"))
      (node (ref "R47") (pin "2") (pinfunction "2_2") (pintype "passive"))
    )
    (net (code "85") (name "Net-(J2-Pad2)") (class "Default")
      (node (ref "J2") (pin "2") (pinfunction "2_2") (pintype "passive"))
      (node (ref "R48") (pin "1") (pinfunction "1_1") (pintype "passive"))
    )
    (net (code "86") (name "Net-(J2-Pad3)") (class "Default")
      (node (ref "J2") (pin "3") (pinfunction "3_3") (pintype "passive"))
      (node (ref "R49") (pin "2") (pinfunction "2_2") (pintype "passive"))
    )
    (net (code "87") (name "Net-(J2-Pad4)") (class "Default")
      (node (ref "J2") (pin "4") (pinfunction "4_4") (pintype "passive"))
      (node (ref "R50") (pin "1") (pinfunction "1_1") (pintype "passive"))
    )
    (net (code "88") (name "Net-(J2-Pad5)") (class "Default")
      (node (ref "J2") (pin "5") (pinfunction "5_5") (pintype "passive"))
      (node (ref "R51") (pin "2") (pinfunction "2_2") (pintype "passive"))
    )
    (net (code "89") (name "Net-(J2-Pad6)") (class "Default")
      (node (ref "J2") (pin "6") (pinfunction "6_6") (pintype "passive"))
      (node (ref "R52") (pin "1") (pinfunction "1_1") (pintype "passive"))
    )
    (net (code "90") (name "Net-(J2-Pad7)") (class "Default")
      (node (ref "J2") (pin "7") (pinfunction "7_7") (pintype "passive"))
      (node (ref "R53") (pin "2") (pinfunction "2_2") (pintype "passive"))
    )
    (net (code "91") (name "Net-(J2-Pad8)") (class "Default")
      (node (ref "J2") (pin "8") (pinfunction "8_8") (pintype "passive"))
      (node (ref "R54") (pin "1") (pinfunction "1_1") (pintype "passive"))
    )
    (net (code "92") (name "Net-(J4-S1)") (class "Default")
      (node (ref "C5") (pin "2") (pinfunction "2_2") (pintype "passive"))
      (node (ref "J4") (pin "6") (pinfunction "S1_6") (pintype "passive"))
      (node (ref "J4") (pin "7") (pinfunction "S2_7") (pintype "passive"))
      (node (ref "J4") (pin "8") (pinfunction "S3_8") (pintype "passive"))
      (node (ref "J4") (pin "9") (pinfunction "S4_9") (pintype "passive"))
      (node (ref "R2") (pin "2") (pinfunction "2_2") (pintype "passive"))
    )
    (net (code "93") (name "Net-(J5-Pad1)") (class "Default")
      (node (ref "J5") (pin "1") (pinfunction "1_1") (pintype "passive"))
      (node (ref "R55") (pin "2") (pinfunction "2_2") (pintype "passive"))
    )
    (net (code "94") (name "Net-(J5-Pad2)") (class "Default")
      (node (ref "J5") (pin "2") (pinfunction "2_2") (pintype "passive"))
      (node (ref "R56") (pin "1") (pinfunction "1_1") (pintype "passive"))
    )
    (net (code "95") (name "Net-(J5-Pad3)") (class "Default")
      (node (ref "J5") (pin "3") (pinfunction "3_3") (pintype "passive"))
      (node (ref "R57") (pin "2") (pinfunction "2_2") (pintype "passive"))
    )
    (net (code "96") (name "Net-(J5-Pad4)") (class "Default")
      (node (ref "J5") (pin "4") (pinfunction "4_4") (pintype "passive"))
      (node (ref "R58") (pin "1") (pinfunction "1_1") (pintype "passive"))
    )
    (net (code "97") (name "Net-(J5-Pad5)") (class "Default")
      (node (ref "J5") (pin "5") (pinfunction "5_5") (pintype "passive"))
      (node (ref "R59") (pin "2") (pinfunction "2_2") (pintype "passive"))
    )
    (net (code "98") (name "Net-(J5-Pad6)") (class "Default")
      (node (ref "J5") (pin "6") (pinfunction "6_6") (pintype "passive"))
      (node (ref "R60") (pin "1") (pinfunction "1_1") (pintype "passive"))
    )
    (net (code "99") (name "Net-(J5-Pad7)") (class "Default")
      (node (ref "J5") (pin "7") (pinfunction "7_7") (pintype "passive"))
      (node (ref "R61") (pin "2") (pinfunction "2_2") (pintype "passive"))
    )
    (net (code "100") (name "Net-(J5-Pad8)") (class "Default")
      (node (ref "J5") (pin "8") (pinfunction "8_8") (pintype "passive"))
      (node (ref "R62") (pin "1") (pinfunction "1_1") (pintype "passive"))
    )
    (net (code "101") (name "Net-(J9-5V0)") (class "Default")
      (node (ref "J9") (pin "18") (pinfunction "5V0_18") (pintype "passive"))
      (node (ref "R46") (pin "1") (pinfunction "1_1") (pintype "passive"))
    )
    (net (code "102") (name "Net-(LED1-Anode)") (class "Default")
      (node (ref "LED1") (pin "2") (pinfunction "Anode_2") (pintype "passive"))
      (node (ref "R7") (pin "1") (pinfunction "1_1") (pintype "passive"))
    )
    (net (code "103") (name "Net-(LED2-Anode)") (class "Default")
      (node (ref "LED2") (pin "2") (pinfunction "Anode_2") (pintype "passive"))
      (node (ref "R8") (pin "1") (pinfunction "1_1") (pintype "passive"))
    )
    (net (code "104") (name "Net-(LED3-Anode)") (class "Default")
      (node (ref "LED3") (pin "2") (pinfunction "Anode_2") (pintype "passive"))
      (node (ref "R41") (pin "1") (pinfunction "1_1") (pintype "passive"))
    )
    (net (code "105") (name "Net-(Q1-Pad2)") (class "Default")
      (node (ref "Q1") (pin "2") (pinfunction "2_2") (pintype "passive"))
      (node (ref "R39") (pin "1") (pinfunction "1_1") (pintype "passive"))
    )
    (net (code "106") (name "Net-(Q1B-2)") (class "Default")
      (node (ref "Q1") (pin "5") (pinfunction "2_5") (pintype "passive"))
      (node (ref "R40") (pin "1") (pinfunction "1_1") (pintype "passive"))
    )
    (net (code "107") (name "Net-(R10-Pad1)") (class "Default")
      (node (ref "R10") (pin "1") (pinfunction "1_1") (pintype "passive"))
      (node (ref "SW1") (pin "2") (pinfunction "2_2") (pintype "passive"))
    )
    (net (code "108") (name "Net-(R11-Pad1)") (class "Default")
      (node (ref "R11") (pin "1") (pinfunction "1_1") (pintype "passive"))
      (node (ref "SW2") (pin "2") (pinfunction "2_2") (pintype "passive"))
    )
    (net (code "109") (name "Net-(R12-Pad1)") (class "Default")
      (node (ref "R12") (pin "1") (pinfunction "1_1") (pintype "passive"))
      (node (ref "SW3") (pin "2") (pinfunction "2_2") (pintype "passive"))
    )
    (net (code "110") (name "Net-(R13-Pad1)") (class "Default")
      (node (ref "R13") (pin "1") (pinfunction "1_1") (pintype "passive"))
      (node (ref "SW4") (pin "2") (pinfunction "2_2") (pintype "passive"))
    )
    (net (code "111") (name "Net-(U1-EECLK)") (class "Default")
      (node (ref "R4") (pin "1") (pinfunction "1_1") (pintype "passive"))
      (node (ref "U1") (pin "62") (pinfunction "EECLK_62") (pintype "passive"))
      (node (ref "U3") (pin "4") (pinfunction "CLK_4") (pintype "passive"))
    )
    (net (code "112") (name "Net-(U1-EECS)") (class "Default")
      (node (ref "R3") (pin "1") (pinfunction "1_1") (pintype "passive"))
      (node (ref "U1") (pin "63") (pinfunction "EECS_63") (pintype "passive"))
      (node (ref "U3") (pin "5") (pinfunction "CS_5") (pintype "passive"))
    )
    (net (code "113") (name "Net-(U1-EEDATA)") (class "Default")
      (node (ref "R5") (pin "1") (pinfunction "1_1") (pintype "passive"))
      (node (ref "R9") (pin "2") (pinfunction "2_2") (pintype "passive"))
      (node (ref "U1") (pin "61") (pinfunction "EEDATA_61") (pintype "passive"))
      (node (ref "U3") (pin "3") (pinfunction "DI_3") (pintype "passive"))
    )
    (net (code "114") (name "Net-(U1-OSCI)") (class "Default")
      (node (ref "C7") (pin "2") (pinfunction "2_2") (pintype "passive"))
      (node (ref "U1") (pin "2") (pinfunction "OSCI_2") (pintype "passive"))
      (node (ref "Y1") (pin "2") (pinfunction "2_2") (pintype "passive"))
    )
    (net (code "115") (name "Net-(U1-OSCO)") (class "Default")
      (node (ref "C8") (pin "2") (pinfunction "2_2") (pintype "passive"))
      (node (ref "U1") (pin "3") (pinfunction "OSCO_3") (pintype "passive"))
      (node (ref "Y1") (pin "1") (pinfunction "1_1") (pintype "passive"))
    )
    (net (code "116") (name "Net-(U1-REF)") (class "Default")
      (node (ref "R1") (pin "2") (pinfunction "2_2") (pintype "passive"))
      (node (ref "U1") (pin "6") (pinfunction "REF_6") (pintype "passive"))
    )
    (net (code "117") (name "Net-(U1-~{RESET})") (class "Default")
      (node (ref "R6") (pin "1") (pinfunction "1_1") (pintype "passive"))
      (node (ref "U1") (pin "14") (pinfunction "~{RESET}_14") (pintype "passive"))
    )
    (net (code "118") (name "Net-(U3-DO)") (class "Default")
      (node (ref "R9") (pin "1") (pinfunction "1_1") (pintype "passive"))
      (node (ref "U3") (pin "1") (pinfunction "DO_1") (pintype "passive"))
    )
    (net (code "119") (name "Net-(U4-EN)") (class "Default")
      (node (ref "R17") (pin "1") (pinfunction "1_1") (pintype "passive"))
      (node (ref "U4") (pin "7") (pinfunction "REFB_7") (pintype "passive"))
      (node (ref "U4") (pin "8") (pinfunction "EN_8") (pintype "passive"))
    )
    (net (code "120") (name "VPHY") (class "Default")
      (node (ref "C2") (pin "2") (pinfunction "2_2") (pintype "passive"))
      (node (ref "C3") (pin "1") (pinfunction "1_1") (pintype "passive"))
      (node (ref "FB2") (pin "2") (pinfunction "2_2") (pintype "passive"))
      (node (ref "U1") (pin "4") (pinfunction "VPHY_4") (pintype "passive"))
    )
    (net (code "121") (name "VPLL") (class "Default")
      (node (ref "C12") (pin "1") (pinfunction "1_1") (pintype "passive"))
      (node (ref "C4") (pin "2") (pinfunction "2_2") (pintype "passive"))
      (node (ref "FB1") (pin "2") (pinfunction "2_2") (pintype "passive"))
      (node (ref "U1") (pin "9") (pinfunction "VPLL_9") (pintype "passive"))
    )
    (net (code "122") (name "unconnected-(J3-Pad10)") (class "Default")
      (node (ref "J3") (pin "10") (pinfunction "10_10") (pintype "passive+no_connect"))
    )
    (net (code "123") (name "unconnected-(J4-ID-Pad4)") (class "Default")
      (node (ref "J4") (pin "4") (pinfunction "ID_4") (pintype "passive+no_connect"))
    )
    (net (code "124") (name "unconnected-(J6-Pad10)") (class "Default")
      (node (ref "J6") (pin "10") (pinfunction "10_10") (pintype "passive+no_connect"))
    )
    (net (code "125") (name "unconnected-(J8-Pad10)") (class "Default")
      (node (ref "J8") (pin "10") (pinfunction "10_10") (pintype "passive+no_connect"))
    )
    (net (code "126") (name "unconnected-(J9-RES-Pad14)") (class "Default")
      (node (ref "J9") (pin "14") (pinfunction "RES_14") (pintype "passive+no_connect"))
    )
    (net (code "127") (name "unconnected-(MH1-Pad1)") (class "Default")
      (node (ref "MH1") (pin "1") (pinfunction "1_1") (pintype "passive+no_connect"))
    )
    (net (code "128") (name "unconnected-(MH2-Pad1)") (class "Default")
      (node (ref "MH2") (pin "1") (pinfunction "1_1") (pintype "passive+no_connect"))
    )
    (net (code "129") (name "unconnected-(MH3-Pad1)") (class "Default")
      (node (ref "MH3") (pin "1") (pinfunction "1_1") (pintype "passive+no_connect"))
    )
    (net (code "130") (name "unconnected-(MH4-Pad1)") (class "Default")
      (node (ref "MH4") (pin "1") (pinfunction "1_1") (pintype "passive+no_connect"))
    )
    (net (code "131") (name "unconnected-(U1-ACBUS0-Pad26)") (class "Default")
      (node (ref "U1") (pin "26") (pinfunction "ACBUS0_26") (pintype "passive+no_connect"))
    )
    (net (code "132") (name "unconnected-(U1-ACBUS1-Pad27)") (class "Default")
      (node (ref "U1") (pin "27") (pinfunction "ACBUS1_27") (pintype "passive+no_connect"))
    )
    (net (code "133") (name "unconnected-(U1-ACBUS2-Pad28)") (class "Default")
      (node (ref "U1") (pin "28") (pinfunction "ACBUS2_28") (pintype "passive+no_connect"))
    )
    (net (code "134") (name "unconnected-(U1-ACBUS3-Pad29)") (class "Default")
      (node (ref "U1") (pin "29") (pinfunction "ACBUS3_29") (pintype "passive+no_connect"))
    )
    (net (code "135") (name "unconnected-(U1-ACBUS4-Pad30)") (class "Default")
      (node (ref "U1") (pin "30") (pinfunction "ACBUS4_30") (pintype "passive+no_connect"))
    )
    (net (code "136") (name "unconnected-(U1-ACBUS6-Pad33)") (class "Default")
      (node (ref "U1") (pin "33") (pinfunction "ACBUS6_33") (pintype "passive+no_connect"))
    )
    (net (code "137") (name "unconnected-(U1-ACBUS7-Pad34)") (class "Default")
      (node (ref "U1") (pin "34") (pinfunction "ACBUS7_34") (pintype "passive+no_connect"))
    )
    (net (code "138") (name "unconnected-(U1-ADBUS4-Pad21)") (class "Default")
      (node (ref "U1") (pin "21") (pinfunction "ADBUS4_21") (pintype "passive+no_connect"))
    )
    (net (code "139") (name "unconnected-(U1-ADBUS5-Pad22)") (class "Default")
      (node (ref "U1") (pin "22") (pinfunction "ADBUS5_22") (pintype "passive+no_connect"))
    )
    (net (code "140") (name "unconnected-(U1-ADBUS6-Pad23)") (class "Default")
      (node (ref "U1") (pin "23") (pinfunction "ADBUS6_23") (pintype "passive+no_connect"))
    )
    (net (code "141") (name "unconnected-(U1-ADBUS7-Pad24)") (class "Default")
      (node (ref "U1") (pin "24") (pinfunction "ADBUS7_24") (pintype "passive+no_connect"))
    )
    (net (code "142") (name "unconnected-(U1-BCBUS0-Pad48)") (class "Default")
      (node (ref "U1") (pin "48") (pinfunction "BCBUS0_48") (pintype "passive+no_connect"))
    )
    (net (code "143") (name "unconnected-(U1-BCBUS1-Pad52)") (class "Default")
      (node (ref "U1") (pin "52") (pinfunction "BCBUS1_52") (pintype "passive+no_connect"))
    )
    (net (code "144") (name "unconnected-(U1-BCBUS2-Pad53)") (class "Default")
      (node (ref "U1") (pin "53") (pinfunction "BCBUS2_53") (pintype "passive+no_connect"))
    )
    (net (code "145") (name "unconnected-(U1-BCBUS5-Pad57)") (class "Default")
      (node (ref "U1") (pin "57") (pinfunction "BCBUS5_57") (pintype "passive+no_connect"))
    )
    (net (code "146") (name "unconnected-(U1-BCBUS6-Pad58)") (class "Default")
      (node (ref "U1") (pin "58") (pinfunction "BCBUS6_58") (pintype "passive+no_connect"))
    )
    (net (code "147") (name "unconnected-(U1-BCBUS7-Pad59)") (class "Default")
      (node (ref "U1") (pin "59") (pinfunction "BCBUS7_59") (pintype "passive+no_connect"))
    )
    (net (code "148") (name "unconnected-(U1-BDBUS4-Pad43)") (class "Default")
      (node (ref "U1") (pin "43") (pinfunction "BDBUS4_43") (pintype "passive+no_connect"))
    )
    (net (code "149") (name "unconnected-(U1-BDBUS5-Pad44)") (class "Default")
      (node (ref "U1") (pin "44") (pinfunction "BDBUS5_44") (pintype "passive+no_connect"))
    )
    (net (code "150") (name "unconnected-(U1-BDBUS6-Pad45)") (class "Default")
      (node (ref "U1") (pin "45") (pinfunction "BDBUS6_45") (pintype "passive+no_connect"))
    )
    (net (code "151") (name "unconnected-(U1-BDBUS7-Pad46)") (class "Default")
      (node (ref "U1") (pin "46") (pinfunction "BDBUS7_46") (pintype "passive+no_connect"))
    )
    (net (code "152") (name "unconnected-(U1-~{PWREN}-Pad60)") (class "Default")
      (node (ref "U1") (pin "60") (pinfunction "~{PWREN}_60") (pintype "passive+no_connect"))
    )
    (net (code "153") (name "unconnected-(U1-~{SUSPEND}-Pad36)") (class "Default")
      (node (ref "U1") (pin "36") (pinfunction "~{SUSPEND}_36") (pintype "passive+no_connect"))
    )
  )
)
